# Power_Supply.net
KiCad netlist of a schematic drawn in Altium Designer
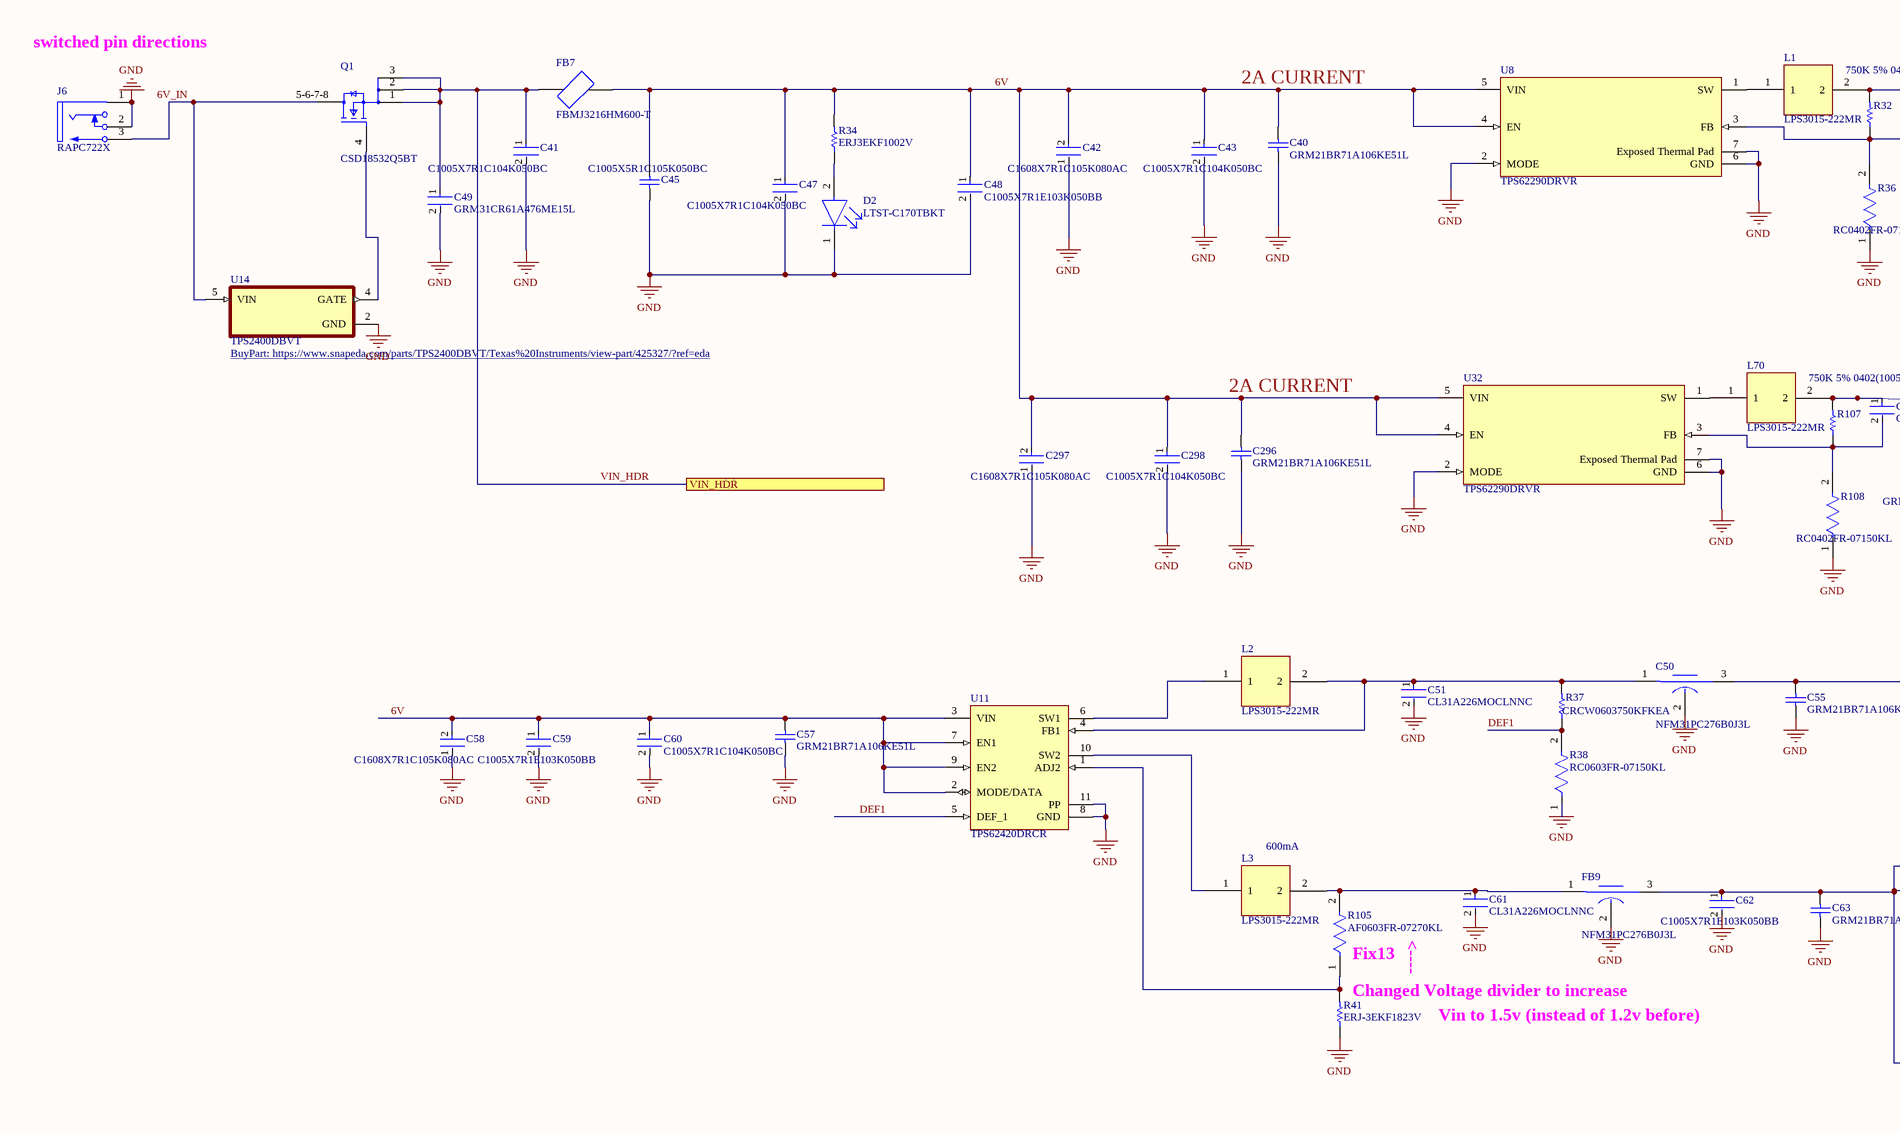
[diagram p0: Power_Supply.SchDoc, top left]
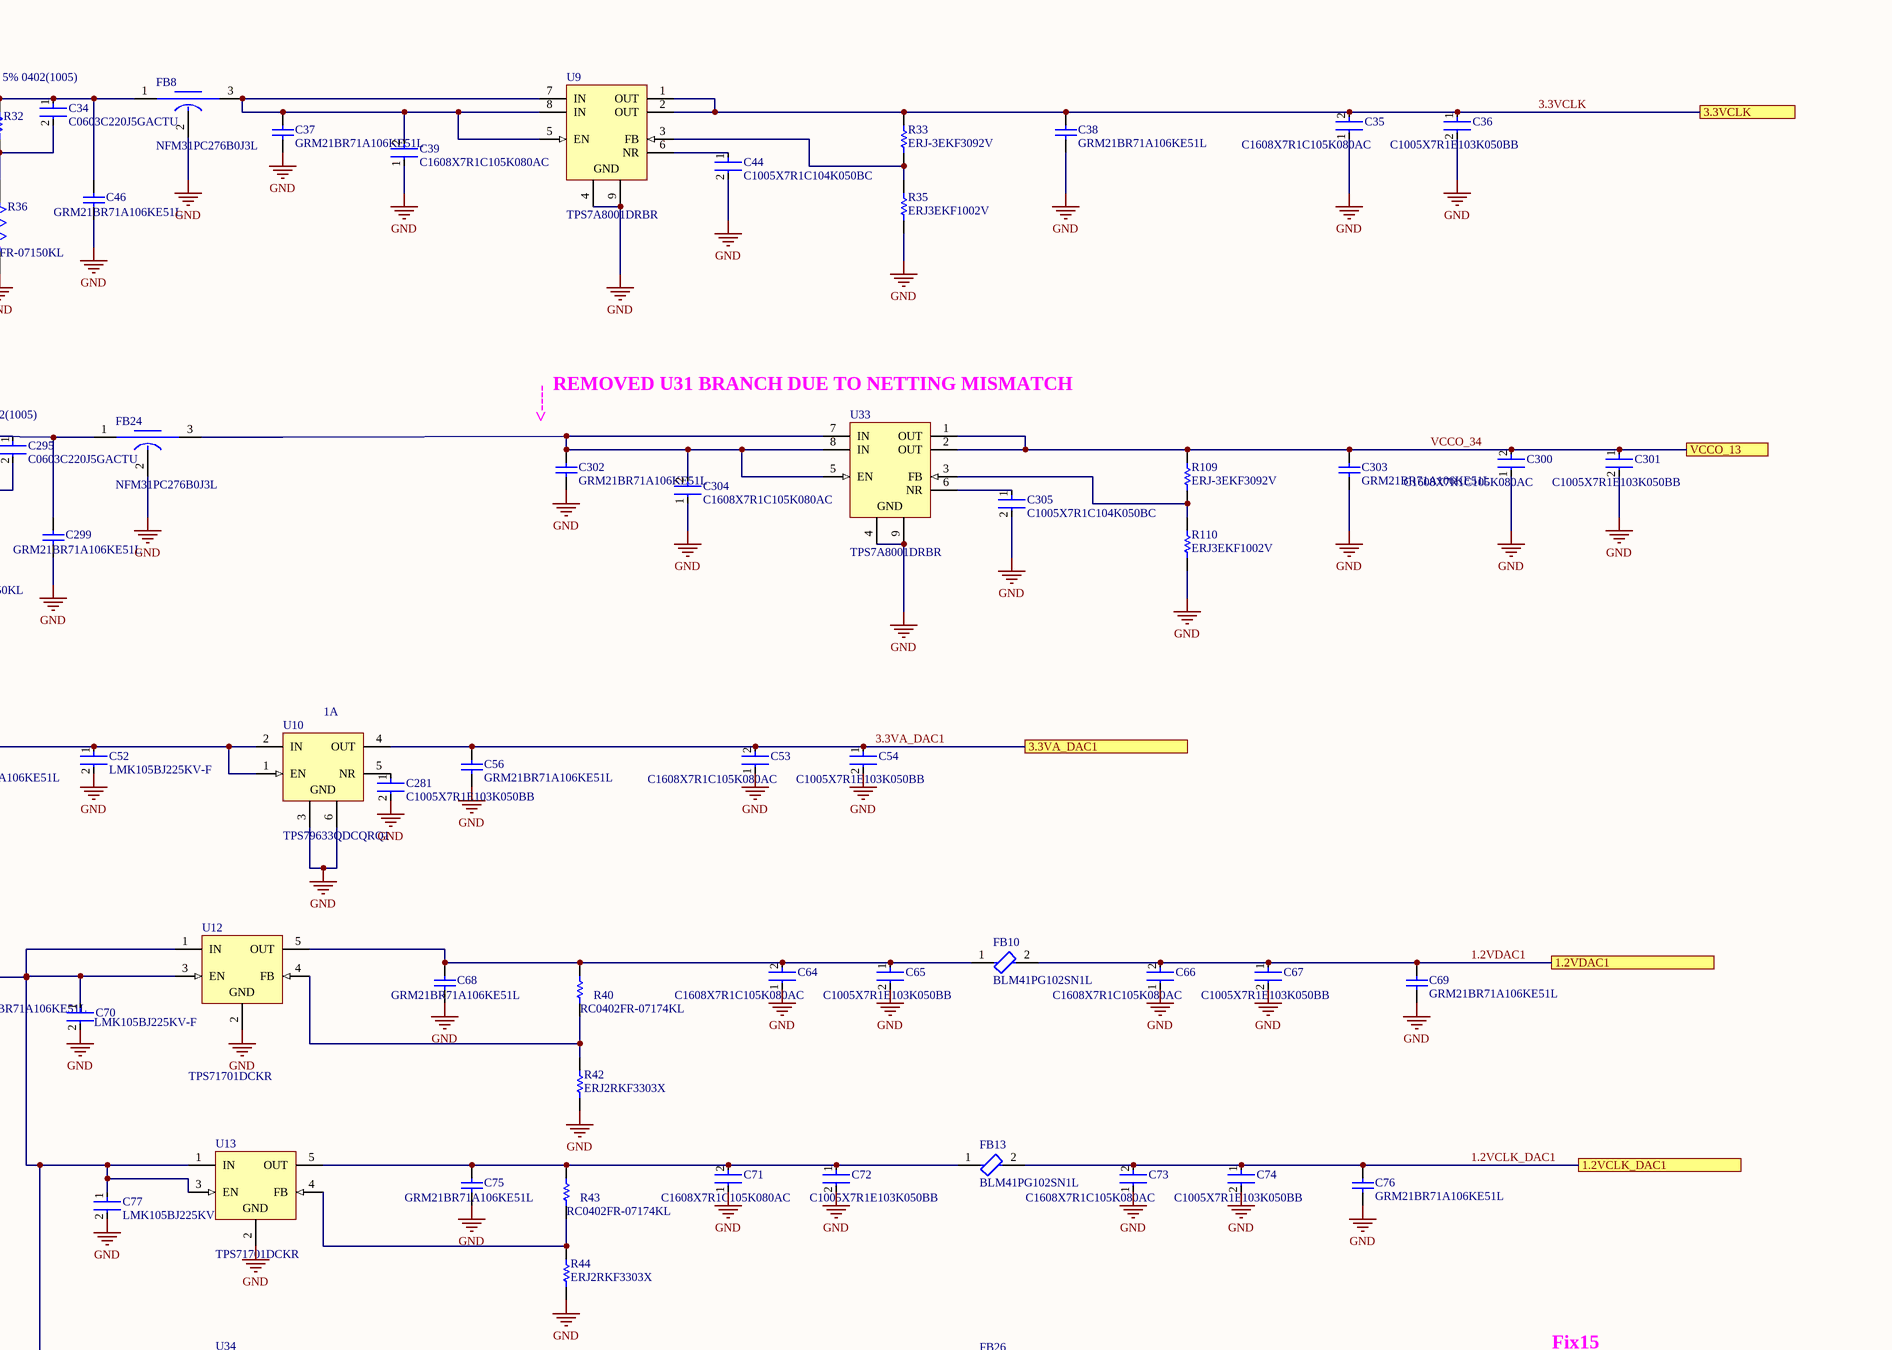
[diagram p1: Power_Supply.SchDoc, top right]
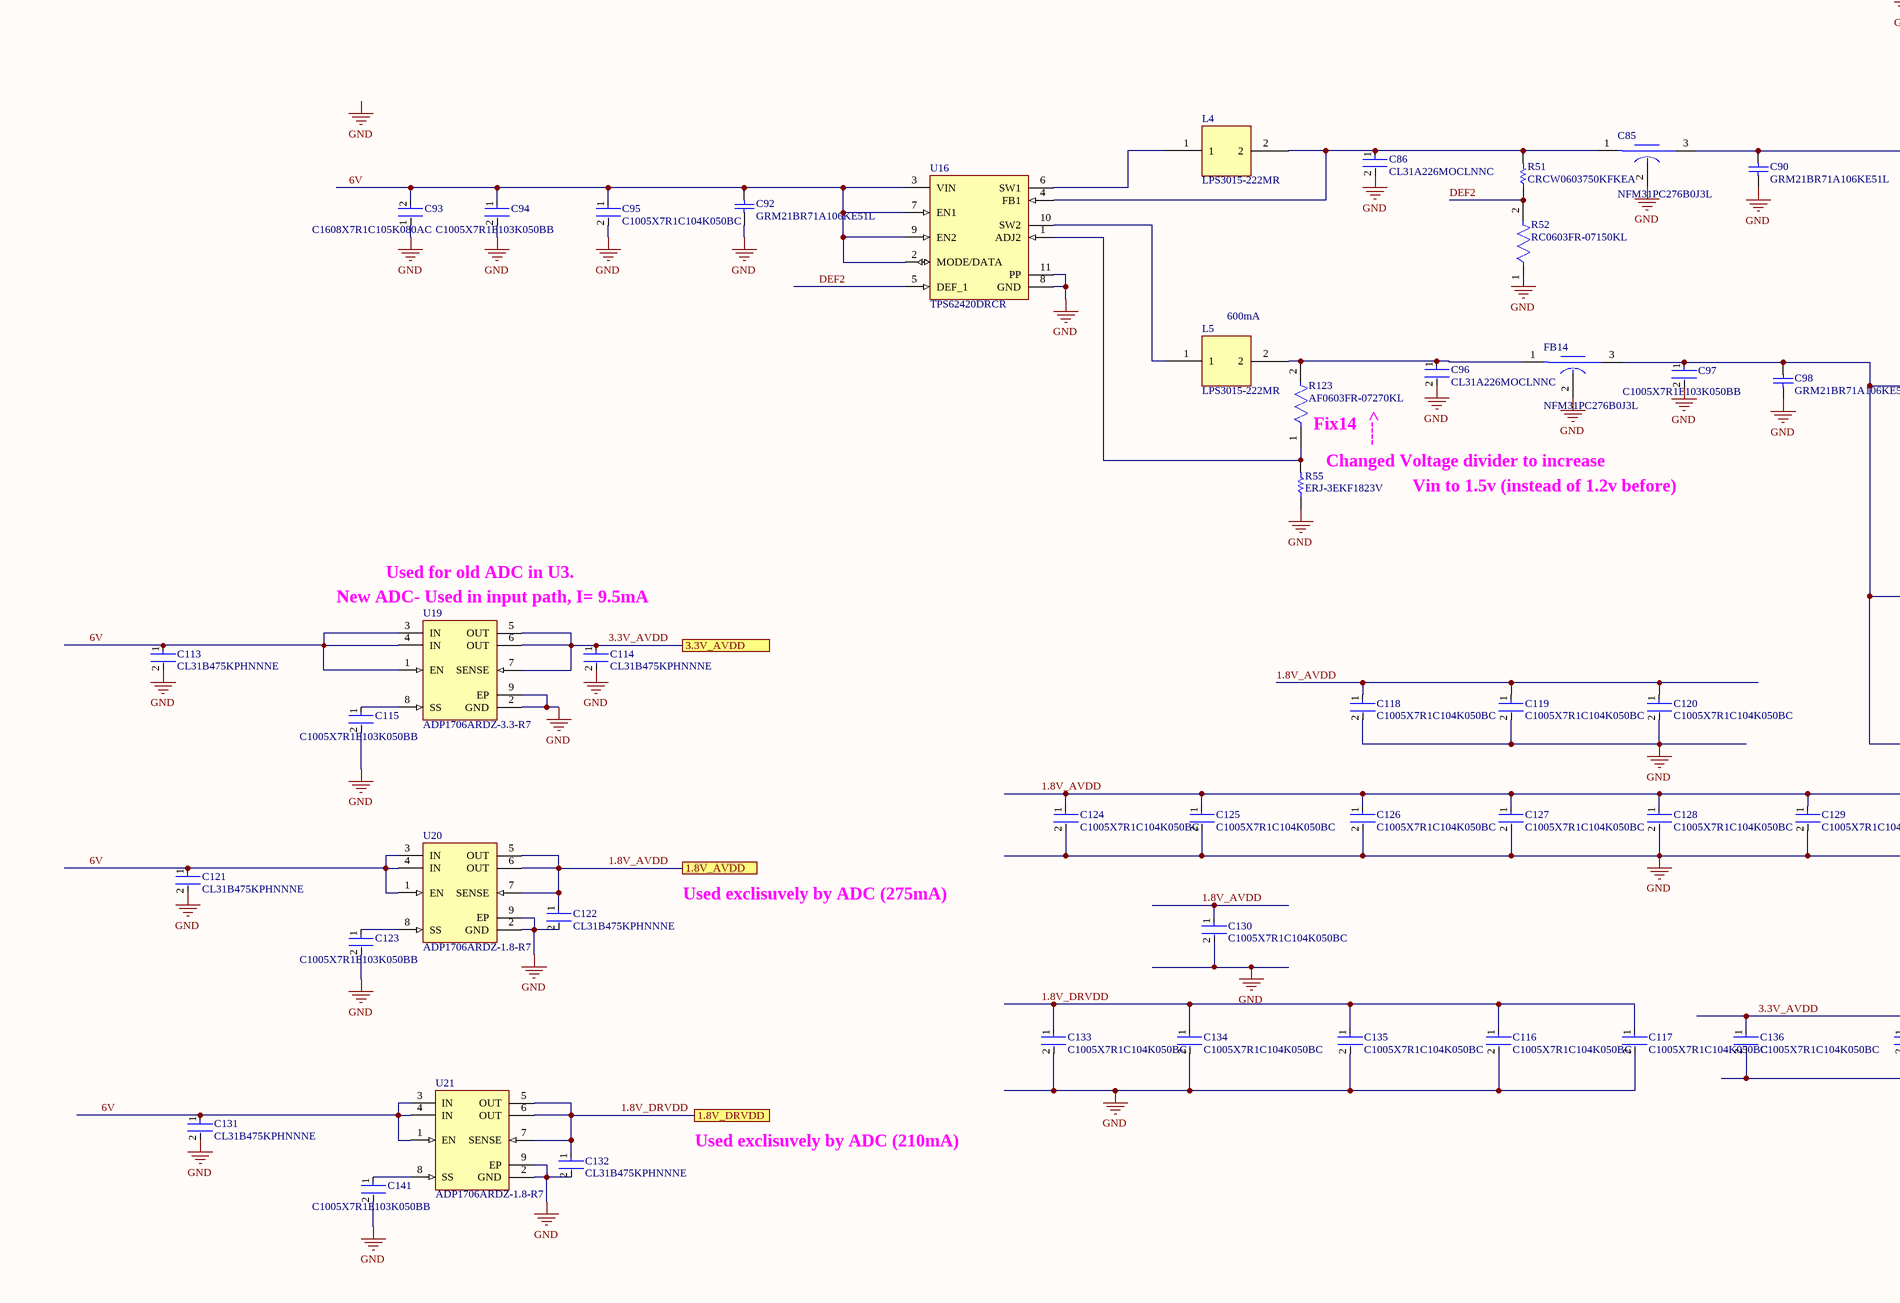
[diagram p2: Power_Supply.SchDoc, bottom left]
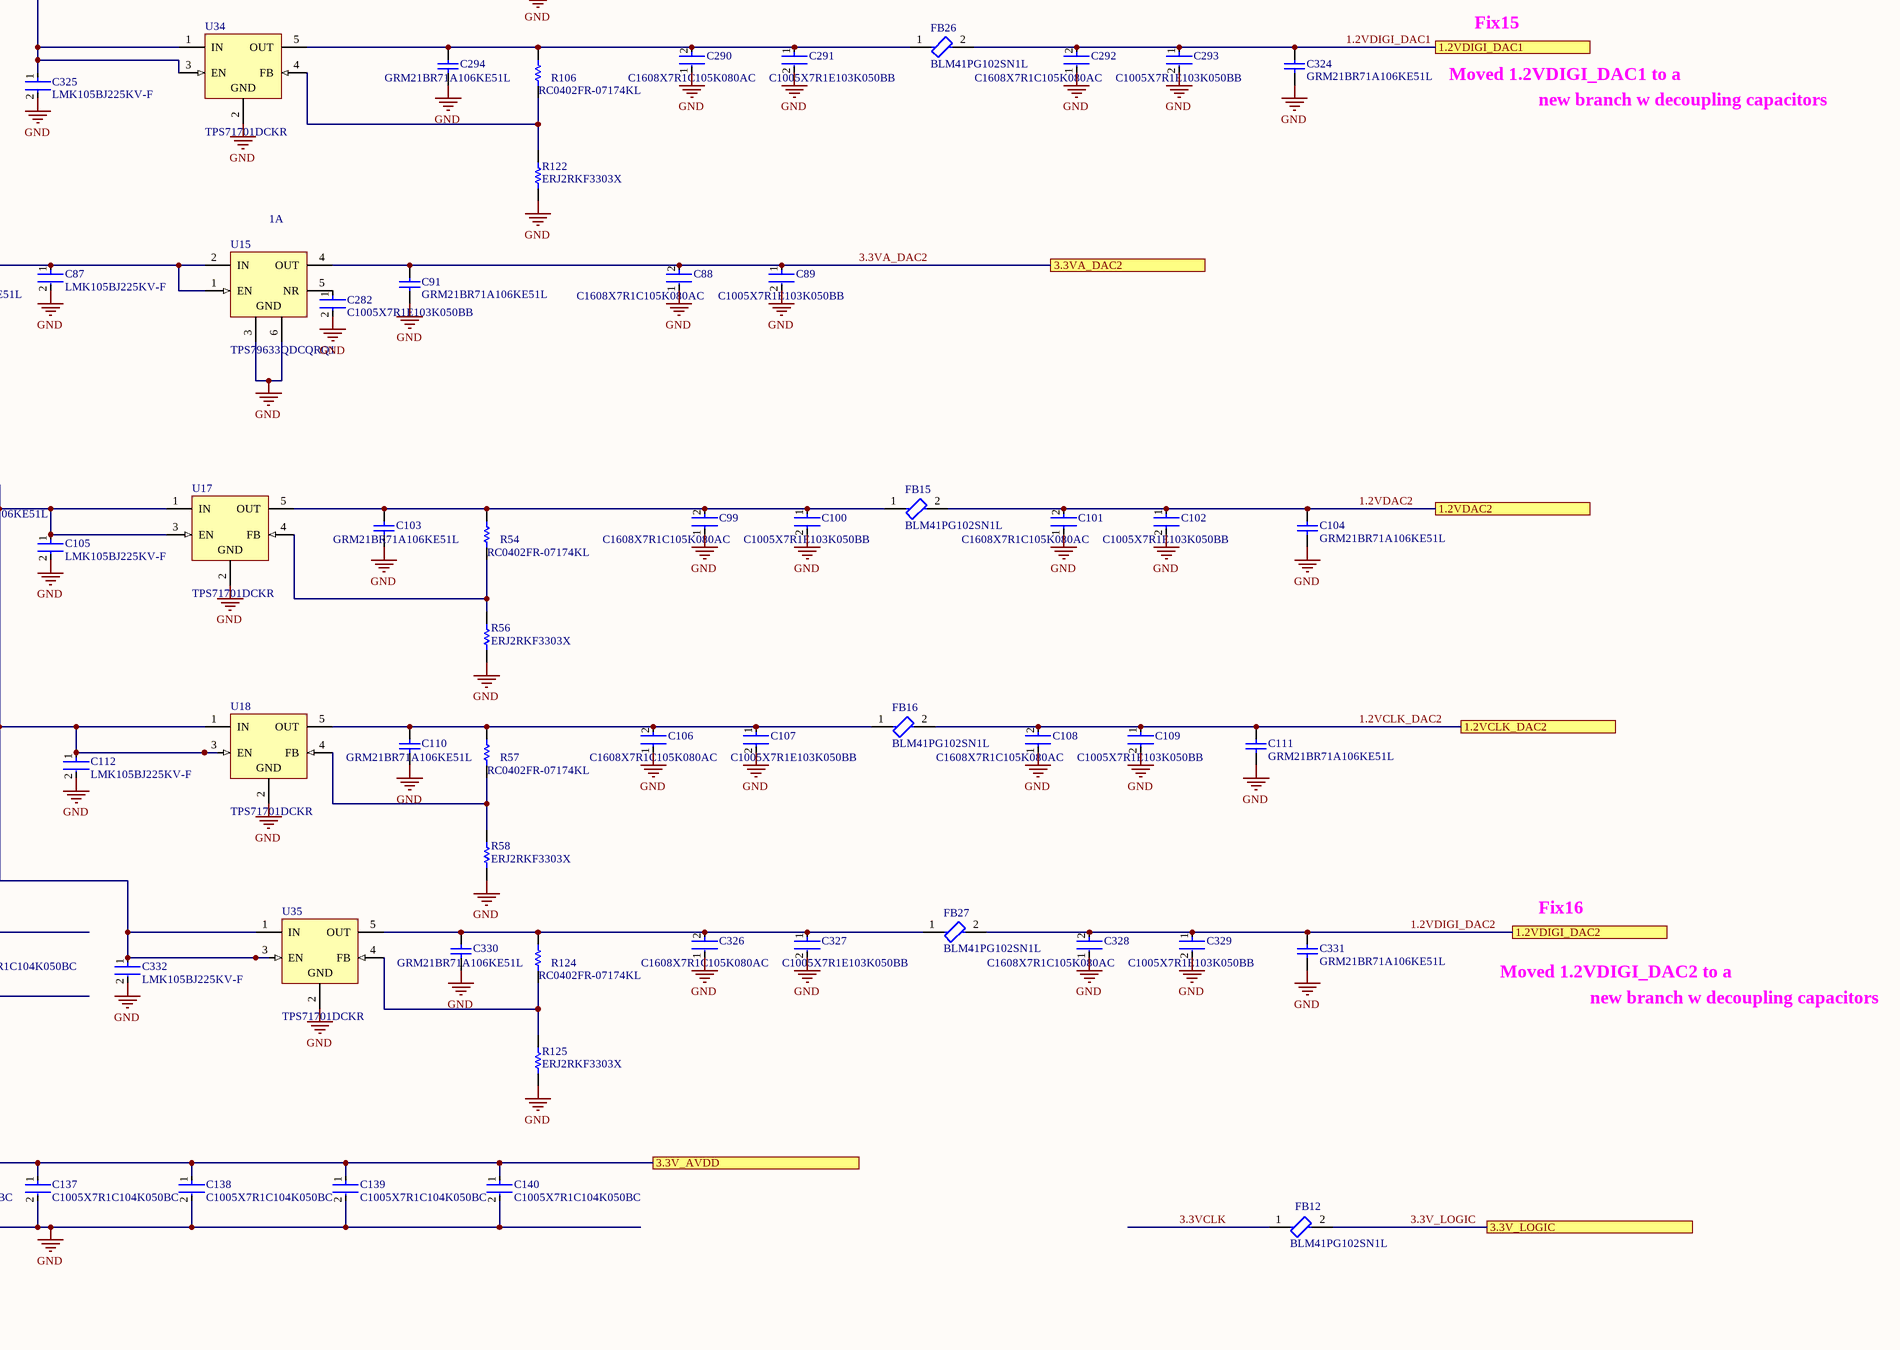
[diagram p3: Power_Supply.SchDoc, bottom right]

(export (version "E")
  (design (tool "Eeschema 10.0.6"))
  (components
    (comp (ref "C34")
      (value "C0603C220J5GACTU")
      (footprint "C0603")
      (description "Cap Ceramic 22pF 50V C0G 5% SMD 0603 125°C Paper T/R")
      (fields (field (name "TOLERANCE") "0.05") (field (name "MANUFACTURER") "KEMET"))
      (libsource (lib "DACֹֹ_Sources") (part "b4654b650e69147ec39a6b967a45e02"))
    )
    (comp (ref "C35")
      (value "C1608X7R1C105K080AC")
      (footprint "C0603")
      (description "Multilayer Ceramic Capacitors 1μF ±10% 16V X7R SMD 0603")
      (fields (field (name "VOLTAGE") "16V") (field (name "TOLERANCE") "10%"))
      (libsource (lib "DACֹֹ_Sources") (part "236180d848d6139a670b325ea6854c9"))
    )
    (comp (ref "C36")
      (value "C1005X7R1E103K050BB")
      (footprint "C0402")
      (description "Multilayer Ceramic Capacitors 10nF ±10% 25V X7R SMD 0402")
      (fields (field (name "TOLERANCE") "10%") (field (name "VOLTAGE") "25V"))
      (libsource (lib "DACֹֹ_Sources") (part "b4654b650e69147ec39a6b967a45e02"))
    )
    (comp (ref "C37")
      (value "GRM21BR71A106KE51L")
      (footprint "C0805")
      (fields (field (name "MANUFACTURER") "Murata"))
      (libsource (lib "DACֹֹ_Sources") (part "CAP"))
    )
    (comp (ref "C38")
      (value "GRM21BR71A106KE51L")
      (footprint "C0805")
      (fields (field (name "MANUFACTURER") "Murata"))
      (libsource (lib "DACֹֹ_Sources") (part "CAP"))
    )
    (comp (ref "C39")
      (value "C1608X7R1C105K080AC")
      (footprint "C0603")
      (description "Multilayer Ceramic Capacitors 1μF ±10% 16V X7R SMD 0603")
      (fields (field (name "VOLTAGE") "16V") (field (name "TOLERANCE") "10%"))
      (libsource (lib "DACֹֹ_Sources") (part "236180d848d6139a670b325ea6854c9"))
    )
    (comp (ref "C40")
      (value "GRM21BR71A106KE51L")
      (footprint "C0805")
      (fields (field (name "MANUFACTURER") "Murata"))
      (libsource (lib "DACֹֹ_Sources") (part "CAP"))
    )
    (comp (ref "C41")
      (value "C1005X7R1C104K050BC")
      (footprint "C0402")
      (description "Multilayer Ceramic Capacitors 100nF ±10% 16V X7R SMD 0402")
      (fields (field (name "VOLTAGE") "16V") (field (name "TOLERANCE") "10%"))
      (libsource (lib "DACֹֹ_Sources") (part "b4654b650e69147ec39a6b967a45e02"))
    )
    (comp (ref "C42")
      (value "C1608X7R1C105K080AC")
      (footprint "C0603")
      (description "Multilayer Ceramic Capacitors 1μF ±10% 16V X7R SMD 0603")
      (fields (field (name "VOLTAGE") "16V") (field (name "TOLERANCE") "10%"))
      (libsource (lib "DACֹֹ_Sources") (part "236180d848d6139a670b325ea6854c9"))
    )
    (comp (ref "C43")
      (value "C1005X7R1C104K050BC")
      (footprint "C0402")
      (description "Multilayer Ceramic Capacitors 100nF ±10% 16V X7R SMD 0402")
      (fields (field (name "VOLTAGE") "16V") (field (name "TOLERANCE") "10%"))
      (libsource (lib "DACֹֹ_Sources") (part "b4654b650e69147ec39a6b967a45e02"))
    )
    (comp (ref "C44")
      (value "C1005X7R1C104K050BC")
      (footprint "C0402")
      (description "Multilayer Ceramic Capacitors 100nF ±10% 16V X7R SMD 0402")
      (fields (field (name "VOLTAGE") "16V") (field (name "TOLERANCE") "10%"))
      (libsource (lib "DACֹֹ_Sources") (part "b4654b650e69147ec39a6b967a45e02"))
    )
    (comp (ref "C45")
      (value "C1005X5R1C105K050BC")
      (footprint "C0402")
      (description "Chip Capacitor, 1 uF, +/- 10%, 16 V, -55 to 85 degC, 0402 (1005 Metric), RoHS, Tape and Reel")
      (fields
        (field (name "TOLERANCE") "±10%")
        (field (name "PCN PART NUMBER") "MLCCPartNumberChange30/Nov/2012")
      )
      (libsource (lib "DACֹֹ_Sources") (part "CAP-NP-2"))
    )
    (comp (ref "C46")
      (value "GRM21BR71A106KE51L")
      (footprint "C0805")
      (fields (field (name "MANUFACTURER") "Murata"))
      (libsource (lib "DACֹֹ_Sources") (part "CAP"))
    )
    (comp (ref "C47")
      (value "C1005X7R1C104K050BC")
      (footprint "C0402")
      (description "Multilayer Ceramic Capacitors 100nF ±10% 16V X7R SMD 0402")
      (fields (field (name "VOLTAGE") "16V") (field (name "TOLERANCE") "10%"))
      (libsource (lib "DACֹֹ_Sources") (part "b4654b650e69147ec39a6b967a45e02"))
    )
    (comp (ref "C48")
      (value "C1005X7R1E103K050BB")
      (footprint "C0402")
      (description "Multilayer Ceramic Capacitors 10nF ±10% 25V X7R SMD 0402")
      (fields (field (name "TOLERANCE") "10%") (field (name "VOLTAGE") "25V"))
      (libsource (lib "DACֹֹ_Sources") (part "b4654b650e69147ec39a6b967a45e02"))
    )
    (comp (ref "C49")
      (value "GRM31CR61A476ME15L")
      (footprint "C1206")
      (description "Chip Multilayer Ceramic Capacitors for General Purpose, 1206, 47uF, X5R, 15%, 20%, 10V")
      (fields (field (name "TOLERANCE") "20%") (field (name "VOLTAGE") "10V"))
      (libsource (lib "DACֹֹ_Sources") (part "02cd4be3c70576c341d710602a673aa"))
    )
    (comp (ref "C50")
      (value "NFM31PC276B0J3L")
      (footprint "FP-NFM31-0_2-MFG")
      (fields (field (name "VOLTAGE") "6.3V") (field (name "TOLERANCE") "20%"))
      (libsource (lib "DACֹֹ_Sources") (part "968ca41a07abfef6fd4f7114a56c54f"))
    )
    (comp (ref "C51")
      (value "CL31A226MOCLNNC")
      (footprint "C1206")
      (description "Cap Ceramic 22uF 16V X5R ±20% SMD 1206 +85°C Embossed T/R")
      (fields (field (name "TOLERANCE") "20%") (field (name "VOLTAGE") "16V"))
      (libsource (lib "DACֹֹ_Sources") (part "b4654b650e69147ec39a6b967a45e02"))
    )
    (comp (ref "C52")
      (value "LMK105BJ225KV-F")
      (footprint "C0402")
      (description "None")
      (fields (field (name "TOLERANCE") "10%"))
      (libsource (lib "DACֹֹ_Sources") (part "b4654b650e69147ec39a6b967a45e02"))
    )
    (comp (ref "C53")
      (value "C1608X7R1C105K080AC")
      (footprint "C0603")
      (description "Multilayer Ceramic Capacitors 1μF ±10% 16V X7R SMD 0603")
      (fields (field (name "VOLTAGE") "16V") (field (name "TOLERANCE") "10%"))
      (libsource (lib "DACֹֹ_Sources") (part "236180d848d6139a670b325ea6854c9"))
    )
    (comp (ref "C54")
      (value "C1005X7R1E103K050BB")
      (footprint "C0402")
      (description "Multilayer Ceramic Capacitors 10nF ±10% 25V X7R SMD 0402")
      (fields (field (name "TOLERANCE") "10%") (field (name "VOLTAGE") "25V"))
      (libsource (lib "DACֹֹ_Sources") (part "b4654b650e69147ec39a6b967a45e02"))
    )
    (comp (ref "C55")
      (value "GRM21BR71A106KE51L")
      (footprint "C0805")
      (fields (field (name "MANUFACTURER") "Murata"))
      (libsource (lib "DACֹֹ_Sources") (part "CAP"))
    )
    (comp (ref "C56")
      (value "GRM21BR71A106KE51L")
      (footprint "C0805")
      (fields (field (name "MANUFACTURER") "Murata"))
      (libsource (lib "DACֹֹ_Sources") (part "CAP"))
    )
    (comp (ref "C57")
      (value "GRM21BR71A106KE51L")
      (footprint "C0805")
      (fields (field (name "MANUFACTURER") "Murata"))
      (libsource (lib "DACֹֹ_Sources") (part "CAP"))
    )
    (comp (ref "C58")
      (value "C1608X7R1C105K080AC")
      (footprint "C0603")
      (description "Multilayer Ceramic Capacitors 1μF ±10% 16V X7R SMD 0603")
      (fields (field (name "VOLTAGE") "16V") (field (name "TOLERANCE") "10%"))
      (libsource (lib "DACֹֹ_Sources") (part "236180d848d6139a670b325ea6854c9"))
    )
    (comp (ref "C59")
      (value "C1005X7R1E103K050BB")
      (footprint "C0402")
      (description "Multilayer Ceramic Capacitors 10nF ±10% 25V X7R SMD 0402")
      (fields (field (name "TOLERANCE") "10%") (field (name "VOLTAGE") "25V"))
      (libsource (lib "DACֹֹ_Sources") (part "b4654b650e69147ec39a6b967a45e02"))
    )
    (comp (ref "C60")
      (value "C1005X7R1C104K050BC")
      (footprint "C0402")
      (description "Multilayer Ceramic Capacitors 100nF ±10% 16V X7R SMD 0402")
      (fields (field (name "VOLTAGE") "16V") (field (name "TOLERANCE") "10%"))
      (libsource (lib "DACֹֹ_Sources") (part "b4654b650e69147ec39a6b967a45e02"))
    )
    (comp (ref "C61")
      (value "CL31A226MOCLNNC")
      (footprint "C1206")
      (description "Cap Ceramic 22uF 16V X5R ±20% SMD 1206 +85°C Embossed T/R")
      (fields (field (name "TOLERANCE") "20%") (field (name "VOLTAGE") "16V"))
      (libsource (lib "DACֹֹ_Sources") (part "b4654b650e69147ec39a6b967a45e02"))
    )
    (comp (ref "C62")
      (value "C1005X7R1E103K050BB")
      (footprint "C0402")
      (description "Multilayer Ceramic Capacitors 10nF ±10% 25V X7R SMD 0402")
      (fields (field (name "TOLERANCE") "10%") (field (name "VOLTAGE") "25V"))
      (libsource (lib "DACֹֹ_Sources") (part "b4654b650e69147ec39a6b967a45e02"))
    )
    (comp (ref "C63")
      (value "GRM21BR71A106KE51L")
      (footprint "C0805")
      (fields (field (name "MANUFACTURER") "Murata"))
      (libsource (lib "DACֹֹ_Sources") (part "CAP"))
    )
    (comp (ref "C64")
      (value "C1608X7R1C105K080AC")
      (footprint "C0603")
      (description "Multilayer Ceramic Capacitors 1μF ±10% 16V X7R SMD 0603")
      (fields (field (name "VOLTAGE") "16V") (field (name "TOLERANCE") "10%"))
      (libsource (lib "DACֹֹ_Sources") (part "236180d848d6139a670b325ea6854c9"))
    )
    (comp (ref "C65")
      (value "C1005X7R1E103K050BB")
      (footprint "C0402")
      (description "Multilayer Ceramic Capacitors 10nF ±10% 25V X7R SMD 0402")
      (fields (field (name "TOLERANCE") "10%") (field (name "VOLTAGE") "25V"))
      (libsource (lib "DACֹֹ_Sources") (part "b4654b650e69147ec39a6b967a45e02"))
    )
    (comp (ref "C66")
      (value "C1608X7R1C105K080AC")
      (footprint "C0603")
      (description "Multilayer Ceramic Capacitors 1μF ±10% 16V X7R SMD 0603")
      (fields (field (name "VOLTAGE") "16V") (field (name "TOLERANCE") "10%"))
      (libsource (lib "DACֹֹ_Sources") (part "236180d848d6139a670b325ea6854c9"))
    )
    (comp (ref "C67")
      (value "C1005X7R1E103K050BB")
      (footprint "C0402")
      (description "Multilayer Ceramic Capacitors 10nF ±10% 25V X7R SMD 0402")
      (fields (field (name "TOLERANCE") "10%") (field (name "VOLTAGE") "25V"))
      (libsource (lib "DACֹֹ_Sources") (part "b4654b650e69147ec39a6b967a45e02"))
    )
    (comp (ref "C68")
      (value "GRM21BR71A106KE51L")
      (footprint "C0805")
      (fields (field (name "MANUFACTURER") "Murata"))
      (libsource (lib "DACֹֹ_Sources") (part "CAP"))
    )
    (comp (ref "C69")
      (value "GRM21BR71A106KE51L")
      (footprint "C0805")
      (fields (field (name "MANUFACTURER") "Murata"))
      (libsource (lib "DACֹֹ_Sources") (part "CAP"))
    )
    (comp (ref "C70")
      (value "LMK105BJ225KV-F")
      (footprint "C0402")
      (description "None")
      (fields (field (name "TOLERANCE") "10%"))
      (libsource (lib "Simulation Generic Components") (part "b4654b650e69147ec39a6b967a45e02"))
    )
    (comp (ref "C71")
      (value "C1608X7R1C105K080AC")
      (footprint "C0603")
      (description "Multilayer Ceramic Capacitors 1μF ±10% 16V X7R SMD 0603")
      (fields (field (name "VOLTAGE") "16V") (field (name "TOLERANCE") "10%"))
      (libsource (lib "DACֹֹ_Sources") (part "236180d848d6139a670b325ea6854c9"))
    )
    (comp (ref "C72")
      (value "C1005X7R1E103K050BB")
      (footprint "C0402")
      (description "Multilayer Ceramic Capacitors 10nF ±10% 25V X7R SMD 0402")
      (fields (field (name "TOLERANCE") "10%") (field (name "VOLTAGE") "25V"))
      (libsource (lib "DACֹֹ_Sources") (part "b4654b650e69147ec39a6b967a45e02"))
    )
    (comp (ref "C73")
      (value "C1608X7R1C105K080AC")
      (footprint "C0603")
      (description "Multilayer Ceramic Capacitors 1μF ±10% 16V X7R SMD 0603")
      (fields (field (name "VOLTAGE") "16V") (field (name "TOLERANCE") "10%"))
      (libsource (lib "DACֹֹ_Sources") (part "236180d848d6139a670b325ea6854c9"))
    )
    (comp (ref "C74")
      (value "C1005X7R1E103K050BB")
      (footprint "C0402")
      (description "Multilayer Ceramic Capacitors 10nF ±10% 25V X7R SMD 0402")
      (fields (field (name "TOLERANCE") "10%") (field (name "VOLTAGE") "25V"))
      (libsource (lib "DACֹֹ_Sources") (part "b4654b650e69147ec39a6b967a45e02"))
    )
    (comp (ref "C75")
      (value "GRM21BR71A106KE51L")
      (footprint "C0805")
      (fields (field (name "MANUFACTURER") "Murata"))
      (libsource (lib "DACֹֹ_Sources") (part "CAP"))
    )
    (comp (ref "C76")
      (value "GRM21BR71A106KE51L")
      (footprint "C0805")
      (fields (field (name "MANUFACTURER") "Murata"))
      (libsource (lib "DACֹֹ_Sources") (part "CAP"))
    )
    (comp (ref "C77")
      (value "LMK105BJ225KV-F")
      (footprint "C0402")
      (description "None")
      (fields (field (name "TOLERANCE") "10%"))
      (libsource (lib "DACֹֹ_Sources") (part "b4654b650e69147ec39a6b967a45e02"))
    )
    (comp (ref "C85")
      (value "NFM31PC276B0J3L")
      (footprint "FP-NFM31-0_2-MFG")
      (fields (field (name "VOLTAGE") "6.3V") (field (name "TOLERANCE") "20%"))
      (libsource (lib "DACֹֹ_Sources") (part "968ca41a07abfef6fd4f7114a56c54f"))
    )
    (comp (ref "C86")
      (value "CL31A226MOCLNNC")
      (footprint "C1206")
      (description "Cap Ceramic 22uF 16V X5R ±20% SMD 1206 +85°C Embossed T/R")
      (fields (field (name "TOLERANCE") "20%") (field (name "VOLTAGE") "16V"))
      (libsource (lib "DACֹֹ_Sources") (part "b4654b650e69147ec39a6b967a45e02"))
    )
    (comp (ref "C87")
      (value "LMK105BJ225KV-F")
      (footprint "C0402")
      (description "None")
      (fields (field (name "TOLERANCE") "10%"))
      (libsource (lib "DACֹֹ_Sources") (part "b4654b650e69147ec39a6b967a45e02"))
    )
    (comp (ref "C88")
      (value "C1608X7R1C105K080AC")
      (footprint "C0603")
      (description "Multilayer Ceramic Capacitors 1μF ±10% 16V X7R SMD 0603")
      (fields (field (name "VOLTAGE") "16V") (field (name "TOLERANCE") "10%"))
      (libsource (lib "DACֹֹ_Sources") (part "236180d848d6139a670b325ea6854c9"))
    )
    (comp (ref "C89")
      (value "C1005X7R1E103K050BB")
      (footprint "C0402")
      (description "Multilayer Ceramic Capacitors 10nF ±10% 25V X7R SMD 0402")
      (fields (field (name "TOLERANCE") "10%") (field (name "VOLTAGE") "25V"))
      (libsource (lib "DACֹֹ_Sources") (part "b4654b650e69147ec39a6b967a45e02"))
    )
    (comp (ref "C90")
      (value "GRM21BR71A106KE51L")
      (footprint "C0805")
      (fields (field (name "MANUFACTURER") "Murata"))
      (libsource (lib "DACֹֹ_Sources") (part "CAP"))
    )
    (comp (ref "C91")
      (value "GRM21BR71A106KE51L")
      (footprint "C0805")
      (fields (field (name "MANUFACTURER") "Murata"))
      (libsource (lib "DACֹֹ_Sources") (part "CAP"))
    )
    (comp (ref "C92")
      (value "GRM21BR71A106KE51L")
      (footprint "C0805")
      (fields (field (name "MANUFACTURER") "Murata"))
      (libsource (lib "DACֹֹ_Sources") (part "CAP"))
    )
    (comp (ref "C93")
      (value "C1608X7R1C105K080AC")
      (footprint "C0603")
      (description "Multilayer Ceramic Capacitors 1μF ±10% 16V X7R SMD 0603")
      (fields (field (name "VOLTAGE") "16V") (field (name "TOLERANCE") "10%"))
      (libsource (lib "DACֹֹ_Sources") (part "236180d848d6139a670b325ea6854c9"))
    )
    (comp (ref "C94")
      (value "C1005X7R1E103K050BB")
      (footprint "C0402")
      (description "Multilayer Ceramic Capacitors 10nF ±10% 25V X7R SMD 0402")
      (fields (field (name "TOLERANCE") "10%") (field (name "VOLTAGE") "25V"))
      (libsource (lib "DACֹֹ_Sources") (part "b4654b650e69147ec39a6b967a45e02"))
    )
    (comp (ref "C95")
      (value "C1005X7R1C104K050BC")
      (footprint "C0402")
      (description "Multilayer Ceramic Capacitors 100nF ±10% 16V X7R SMD 0402")
      (fields (field (name "VOLTAGE") "16V") (field (name "TOLERANCE") "10%"))
      (libsource (lib "DACֹֹ_Sources") (part "b4654b650e69147ec39a6b967a45e02"))
    )
    (comp (ref "C96")
      (value "CL31A226MOCLNNC")
      (footprint "C1206")
      (description "Cap Ceramic 22uF 16V X5R ±20% SMD 1206 +85°C Embossed T/R")
      (fields (field (name "TOLERANCE") "20%") (field (name "VOLTAGE") "16V"))
      (libsource (lib "DACֹֹ_Sources") (part "b4654b650e69147ec39a6b967a45e02"))
    )
    (comp (ref "C97")
      (value "C1005X7R1E103K050BB")
      (footprint "C0402")
      (description "Multilayer Ceramic Capacitors 10nF ±10% 25V X7R SMD 0402")
      (fields (field (name "TOLERANCE") "10%") (field (name "VOLTAGE") "25V"))
      (libsource (lib "DACֹֹ_Sources") (part "b4654b650e69147ec39a6b967a45e02"))
    )
    (comp (ref "C98")
      (value "GRM21BR71A106KE51L")
      (footprint "C0805")
      (fields (field (name "MANUFACTURER") "Murata"))
      (libsource (lib "DACֹֹ_Sources") (part "CAP"))
    )
    (comp (ref "C99")
      (value "C1608X7R1C105K080AC")
      (footprint "C0603")
      (description "Multilayer Ceramic Capacitors 1μF ±10% 16V X7R SMD 0603")
      (fields (field (name "VOLTAGE") "16V") (field (name "TOLERANCE") "10%"))
      (libsource (lib "DACֹֹ_Sources") (part "236180d848d6139a670b325ea6854c9"))
    )
    (comp (ref "C100")
      (value "C1005X7R1E103K050BB")
      (footprint "C0402")
      (description "Multilayer Ceramic Capacitors 10nF ±10% 25V X7R SMD 0402")
      (fields (field (name "TOLERANCE") "10%") (field (name "VOLTAGE") "25V"))
      (libsource (lib "DACֹֹ_Sources") (part "b4654b650e69147ec39a6b967a45e02"))
    )
    (comp (ref "C101")
      (value "C1608X7R1C105K080AC")
      (footprint "C0603")
      (description "Multilayer Ceramic Capacitors 1μF ±10% 16V X7R SMD 0603")
      (fields (field (name "VOLTAGE") "16V") (field (name "TOLERANCE") "10%"))
      (libsource (lib "DACֹֹ_Sources") (part "236180d848d6139a670b325ea6854c9"))
    )
    (comp (ref "C102")
      (value "C1005X7R1E103K050BB")
      (footprint "C0402")
      (description "Multilayer Ceramic Capacitors 10nF ±10% 25V X7R SMD 0402")
      (fields (field (name "TOLERANCE") "10%") (field (name "VOLTAGE") "25V"))
      (libsource (lib "DACֹֹ_Sources") (part "b4654b650e69147ec39a6b967a45e02"))
    )
    (comp (ref "C103")
      (value "GRM21BR71A106KE51L")
      (footprint "C0805")
      (fields (field (name "MANUFACTURER") "Murata"))
      (libsource (lib "DACֹֹ_Sources") (part "CAP"))
    )
    (comp (ref "C104")
      (value "GRM21BR71A106KE51L")
      (footprint "C0805")
      (fields (field (name "MANUFACTURER") "Murata"))
      (libsource (lib "DACֹֹ_Sources") (part "CAP"))
    )
    (comp (ref "C105")
      (value "LMK105BJ225KV-F")
      (footprint "C0402")
      (description "None")
      (fields (field (name "TOLERANCE") "10%"))
      (libsource (lib "DACֹֹ_Sources") (part "b4654b650e69147ec39a6b967a45e02"))
    )
    (comp (ref "C106")
      (value "C1608X7R1C105K080AC")
      (footprint "C0603")
      (description "Multilayer Ceramic Capacitors 1μF ±10% 16V X7R SMD 0603")
      (fields (field (name "VOLTAGE") "16V") (field (name "TOLERANCE") "10%"))
      (libsource (lib "DACֹֹ_Sources") (part "236180d848d6139a670b325ea6854c9"))
    )
    (comp (ref "C107")
      (value "C1005X7R1E103K050BB")
      (footprint "C0402")
      (description "Multilayer Ceramic Capacitors 10nF ±10% 25V X7R SMD 0402")
      (fields (field (name "TOLERANCE") "10%") (field (name "VOLTAGE") "25V"))
      (libsource (lib "DACֹֹ_Sources") (part "b4654b650e69147ec39a6b967a45e02"))
    )
    (comp (ref "C108")
      (value "C1608X7R1C105K080AC")
      (footprint "C0603")
      (description "Multilayer Ceramic Capacitors 1μF ±10% 16V X7R SMD 0603")
      (fields (field (name "VOLTAGE") "16V") (field (name "TOLERANCE") "10%"))
      (libsource (lib "DACֹֹ_Sources") (part "236180d848d6139a670b325ea6854c9"))
    )
    (comp (ref "C109")
      (value "C1005X7R1E103K050BB")
      (footprint "C0402")
      (description "Multilayer Ceramic Capacitors 10nF ±10% 25V X7R SMD 0402")
      (fields (field (name "TOLERANCE") "10%") (field (name "VOLTAGE") "25V"))
      (libsource (lib "DACֹֹ_Sources") (part "b4654b650e69147ec39a6b967a45e02"))
    )
    (comp (ref "C110")
      (value "GRM21BR71A106KE51L")
      (footprint "C0805")
      (fields (field (name "MANUFACTURER") "Murata"))
      (libsource (lib "DACֹֹ_Sources") (part "CAP"))
    )
    (comp (ref "C111")
      (value "GRM21BR71A106KE51L")
      (footprint "C0805")
      (fields (field (name "MANUFACTURER") "Murata"))
      (libsource (lib "DACֹֹ_Sources") (part "CAP"))
    )
    (comp (ref "C112")
      (value "LMK105BJ225KV-F")
      (footprint "C0402")
      (description "None")
      (fields (field (name "TOLERANCE") "10%"))
      (libsource (lib "DACֹֹ_Sources") (part "b4654b650e69147ec39a6b967a45e02"))
    )
    (comp (ref "C113")
      (value "CL31B475KPHNNNE")
      (footprint "C1206")
      (description "Cap Ceramic 4.7uF 10V X7R ±10% SMD 1206 +125°C Embossed T/R")
      (fields (field (name "TOLERANCE") "10%") (field (name "VOLTAGE") "10V"))
      (libsource (lib "DACֹֹ_Sources") (part "b4654b650e69147ec39a6b967a45e02"))
    )
    (comp (ref "C114")
      (value "CL31B475KPHNNNE")
      (footprint "C1206")
      (description "Cap Ceramic 4.7uF 10V X7R ±10% SMD 1206 +125°C Embossed T/R")
      (fields (field (name "TOLERANCE") "10%") (field (name "VOLTAGE") "10V"))
      (libsource (lib "DACֹֹ_Sources") (part "b4654b650e69147ec39a6b967a45e02"))
    )
    (comp (ref "C115")
      (value "C1005X7R1E103K050BB")
      (footprint "C0402")
      (description "Multilayer Ceramic Capacitors 10nF ±10% 25V X7R SMD 0402")
      (fields (field (name "TOLERANCE") "10%") (field (name "VOLTAGE") "25V"))
      (libsource (lib "DACֹֹ_Sources") (part "b4654b650e69147ec39a6b967a45e02"))
    )
    (comp (ref "C116")
      (value "C1005X7R1C104K050BC")
      (footprint "C0402")
      (description "Multilayer Ceramic Capacitors 100nF ±10% 16V X7R SMD 0402")
      (fields (field (name "VOLTAGE") "16V") (field (name "TOLERANCE") "10%"))
      (libsource (lib "DACֹֹ_Sources") (part "b4654b650e69147ec39a6b967a45e02"))
    )
    (comp (ref "C117")
      (value "C1005X7R1C104K050BC")
      (footprint "C0402")
      (description "Multilayer Ceramic Capacitors 100nF ±10% 16V X7R SMD 0402")
      (fields (field (name "VOLTAGE") "16V") (field (name "TOLERANCE") "10%"))
      (libsource (lib "DACֹֹ_Sources") (part "b4654b650e69147ec39a6b967a45e02"))
    )
    (comp (ref "C118")
      (value "C1005X7R1C104K050BC")
      (footprint "C0402")
      (description "Multilayer Ceramic Capacitors 100nF ±10% 16V X7R SMD 0402")
      (fields (field (name "VOLTAGE") "16V") (field (name "TOLERANCE") "10%"))
      (libsource (lib "DACֹֹ_Sources") (part "b4654b650e69147ec39a6b967a45e02"))
    )
    (comp (ref "C119")
      (value "C1005X7R1C104K050BC")
      (footprint "C0402")
      (description "Multilayer Ceramic Capacitors 100nF ±10% 16V X7R SMD 0402")
      (fields (field (name "VOLTAGE") "16V") (field (name "TOLERANCE") "10%"))
      (libsource (lib "DACֹֹ_Sources") (part "b4654b650e69147ec39a6b967a45e02"))
    )
    (comp (ref "C120")
      (value "C1005X7R1C104K050BC")
      (footprint "C0402")
      (description "Multilayer Ceramic Capacitors 100nF ±10% 16V X7R SMD 0402")
      (fields (field (name "VOLTAGE") "16V") (field (name "TOLERANCE") "10%"))
      (libsource (lib "DACֹֹ_Sources") (part "b4654b650e69147ec39a6b967a45e02"))
    )
    (comp (ref "C121")
      (value "CL31B475KPHNNNE")
      (footprint "C1206")
      (description "Cap Ceramic 4.7uF 10V X7R ±10% SMD 1206 +125°C Embossed T/R")
      (fields (field (name "TOLERANCE") "10%") (field (name "VOLTAGE") "10V"))
      (libsource (lib "DACֹֹ_Sources") (part "b4654b650e69147ec39a6b967a45e02"))
    )
    (comp (ref "C122")
      (value "CL31B475KPHNNNE")
      (footprint "C1206")
      (description "Cap Ceramic 4.7uF 10V X7R ±10% SMD 1206 +125°C Embossed T/R")
      (fields (field (name "TOLERANCE") "10%") (field (name "VOLTAGE") "10V"))
      (libsource (lib "DACֹֹ_Sources") (part "b4654b650e69147ec39a6b967a45e02"))
    )
    (comp (ref "C123")
      (value "C1005X7R1E103K050BB")
      (footprint "C0402")
      (description "Multilayer Ceramic Capacitors 10nF ±10% 25V X7R SMD 0402")
      (fields (field (name "TOLERANCE") "10%") (field (name "VOLTAGE") "25V"))
      (libsource (lib "DACֹֹ_Sources") (part "b4654b650e69147ec39a6b967a45e02"))
    )
    (comp (ref "C124")
      (value "C1005X7R1C104K050BC")
      (footprint "C0402")
      (description "Multilayer Ceramic Capacitors 100nF ±10% 16V X7R SMD 0402")
      (fields (field (name "VOLTAGE") "16V") (field (name "TOLERANCE") "10%"))
      (libsource (lib "DACֹֹ_Sources") (part "b4654b650e69147ec39a6b967a45e02"))
    )
    (comp (ref "C125")
      (value "C1005X7R1C104K050BC")
      (footprint "C0402")
      (description "Multilayer Ceramic Capacitors 100nF ±10% 16V X7R SMD 0402")
      (fields (field (name "VOLTAGE") "16V") (field (name "TOLERANCE") "10%"))
      (libsource (lib "DACֹֹ_Sources") (part "b4654b650e69147ec39a6b967a45e02"))
    )
    (comp (ref "C126")
      (value "C1005X7R1C104K050BC")
      (footprint "C0402")
      (description "Multilayer Ceramic Capacitors 100nF ±10% 16V X7R SMD 0402")
      (fields (field (name "VOLTAGE") "16V") (field (name "TOLERANCE") "10%"))
      (libsource (lib "DACֹֹ_Sources") (part "b4654b650e69147ec39a6b967a45e02"))
    )
    (comp (ref "C127")
      (value "C1005X7R1C104K050BC")
      (footprint "C0402")
      (description "Multilayer Ceramic Capacitors 100nF ±10% 16V X7R SMD 0402")
      (fields (field (name "VOLTAGE") "16V") (field (name "TOLERANCE") "10%"))
      (libsource (lib "DACֹֹ_Sources") (part "b4654b650e69147ec39a6b967a45e02"))
    )
    (comp (ref "C128")
      (value "C1005X7R1C104K050BC")
      (footprint "C0402")
      (description "Multilayer Ceramic Capacitors 100nF ±10% 16V X7R SMD 0402")
      (fields (field (name "VOLTAGE") "16V") (field (name "TOLERANCE") "10%"))
      (libsource (lib "DACֹֹ_Sources") (part "b4654b650e69147ec39a6b967a45e02"))
    )
    (comp (ref "C129")
      (value "C1005X7R1C104K050BC")
      (footprint "C0402")
      (description "Multilayer Ceramic Capacitors 100nF ±10% 16V X7R SMD 0402")
      (fields (field (name "VOLTAGE") "16V") (field (name "TOLERANCE") "10%"))
      (libsource (lib "DACֹֹ_Sources") (part "b4654b650e69147ec39a6b967a45e02"))
    )
    (comp (ref "C130")
      (value "C1005X7R1C104K050BC")
      (footprint "C0402")
      (description "Multilayer Ceramic Capacitors 100nF ±10% 16V X7R SMD 0402")
      (fields (field (name "VOLTAGE") "16V") (field (name "TOLERANCE") "10%"))
      (libsource (lib "DACֹֹ_Sources") (part "b4654b650e69147ec39a6b967a45e02"))
    )
    (comp (ref "C131")
      (value "CL31B475KPHNNNE")
      (footprint "C1206")
      (description "Cap Ceramic 4.7uF 10V X7R ±10% SMD 1206 +125°C Embossed T/R")
      (fields (field (name "TOLERANCE") "10%") (field (name "VOLTAGE") "10V"))
      (libsource (lib "DACֹֹ_Sources") (part "b4654b650e69147ec39a6b967a45e02"))
    )
    (comp (ref "C132")
      (value "CL31B475KPHNNNE")
      (footprint "C1206")
      (description "Cap Ceramic 4.7uF 10V X7R ±10% SMD 1206 +125°C Embossed T/R")
      (fields (field (name "TOLERANCE") "10%") (field (name "VOLTAGE") "10V"))
      (libsource (lib "DACֹֹ_Sources") (part "b4654b650e69147ec39a6b967a45e02"))
    )
    (comp (ref "C133")
      (value "C1005X7R1C104K050BC")
      (footprint "C0402")
      (description "Multilayer Ceramic Capacitors 100nF ±10% 16V X7R SMD 0402")
      (fields (field (name "VOLTAGE") "16V") (field (name "TOLERANCE") "10%"))
      (libsource (lib "DACֹֹ_Sources") (part "b4654b650e69147ec39a6b967a45e02"))
    )
    (comp (ref "C134")
      (value "C1005X7R1C104K050BC")
      (footprint "C0402")
      (description "Multilayer Ceramic Capacitors 100nF ±10% 16V X7R SMD 0402")
      (fields (field (name "VOLTAGE") "16V") (field (name "TOLERANCE") "10%"))
      (libsource (lib "DACֹֹ_Sources") (part "b4654b650e69147ec39a6b967a45e02"))
    )
    (comp (ref "C135")
      (value "C1005X7R1C104K050BC")
      (footprint "C0402")
      (description "Multilayer Ceramic Capacitors 100nF ±10% 16V X7R SMD 0402")
      (fields (field (name "VOLTAGE") "16V") (field (name "TOLERANCE") "10%"))
      (libsource (lib "DACֹֹ_Sources") (part "b4654b650e69147ec39a6b967a45e02"))
    )
    (comp (ref "C136")
      (value "C1005X7R1C104K050BC")
      (footprint "C0402")
      (description "Multilayer Ceramic Capacitors 100nF ±10% 16V X7R SMD 0402")
      (fields (field (name "VOLTAGE") "16V") (field (name "TOLERANCE") "10%"))
      (libsource (lib "DACֹֹ_Sources") (part "b4654b650e69147ec39a6b967a45e02"))
    )
    (comp (ref "C137")
      (value "C1005X7R1C104K050BC")
      (footprint "C0402")
      (description "Multilayer Ceramic Capacitors 100nF ±10% 16V X7R SMD 0402")
      (fields (field (name "VOLTAGE") "16V") (field (name "TOLERANCE") "10%"))
      (libsource (lib "DACֹֹ_Sources") (part "b4654b650e69147ec39a6b967a45e02"))
    )
    (comp (ref "C138")
      (value "C1005X7R1C104K050BC")
      (footprint "C0402")
      (description "Multilayer Ceramic Capacitors 100nF ±10% 16V X7R SMD 0402")
      (fields (field (name "VOLTAGE") "16V") (field (name "TOLERANCE") "10%"))
      (libsource (lib "DACֹֹ_Sources") (part "b4654b650e69147ec39a6b967a45e02"))
    )
    (comp (ref "C139")
      (value "C1005X7R1C104K050BC")
      (footprint "C0402")
      (description "Multilayer Ceramic Capacitors 100nF ±10% 16V X7R SMD 0402")
      (fields (field (name "VOLTAGE") "16V") (field (name "TOLERANCE") "10%"))
      (libsource (lib "DACֹֹ_Sources") (part "b4654b650e69147ec39a6b967a45e02"))
    )
    (comp (ref "C140")
      (value "C1005X7R1C104K050BC")
      (footprint "C0402")
      (description "Multilayer Ceramic Capacitors 100nF ±10% 16V X7R SMD 0402")
      (fields (field (name "VOLTAGE") "16V") (field (name "TOLERANCE") "10%"))
      (libsource (lib "DACֹֹ_Sources") (part "b4654b650e69147ec39a6b967a45e02"))
    )
    (comp (ref "C141")
      (value "C1005X7R1E103K050BB")
      (footprint "C0402")
      (description "Multilayer Ceramic Capacitors 10nF ±10% 25V X7R SMD 0402")
      (fields (field (name "TOLERANCE") "10%") (field (name "VOLTAGE") "25V"))
      (libsource (lib "DACֹֹ_Sources") (part "b4654b650e69147ec39a6b967a45e02"))
    )
    (comp (ref "C281")
      (value "C1005X7R1E103K050BB")
      (footprint "C0402")
      (description "Multilayer Ceramic Capacitors 10nF ±10% 25V X7R SMD 0402")
      (fields (field (name "TOLERANCE") "10%") (field (name "VOLTAGE") "25V"))
      (libsource (lib "DACֹֹ_Sources") (part "b4654b650e69147ec39a6b967a45e02"))
    )
    (comp (ref "C282")
      (value "C1005X7R1E103K050BB")
      (footprint "C0402")
      (description "Multilayer Ceramic Capacitors 10nF ±10% 25V X7R SMD 0402")
      (fields (field (name "TOLERANCE") "10%") (field (name "VOLTAGE") "25V"))
      (libsource (lib "DACֹֹ_Sources") (part "b4654b650e69147ec39a6b967a45e02"))
    )
    (comp (ref "C290")
      (value "C1608X7R1C105K080AC")
      (footprint "C0603")
      (description "Multilayer Ceramic Capacitors 1μF ±10% 16V X7R SMD 0603")
      (fields (field (name "VOLTAGE") "16V") (field (name "TOLERANCE") "10%"))
      (libsource (lib "DACֹֹ_Sources") (part "236180d848d6139a670b325ea6854c9"))
    )
    (comp (ref "C291")
      (value "C1005X7R1E103K050BB")
      (footprint "C0402")
      (description "Multilayer Ceramic Capacitors 10nF ±10% 25V X7R SMD 0402")
      (fields (field (name "TOLERANCE") "10%") (field (name "VOLTAGE") "25V"))
      (libsource (lib "DACֹֹ_Sources") (part "b4654b650e69147ec39a6b967a45e02"))
    )
    (comp (ref "C292")
      (value "C1608X7R1C105K080AC")
      (footprint "C0603")
      (description "Multilayer Ceramic Capacitors 1μF ±10% 16V X7R SMD 0603")
      (fields (field (name "VOLTAGE") "16V") (field (name "TOLERANCE") "10%"))
      (libsource (lib "DACֹֹ_Sources") (part "236180d848d6139a670b325ea6854c9"))
    )
    (comp (ref "C293")
      (value "C1005X7R1E103K050BB")
      (footprint "C0402")
      (description "Multilayer Ceramic Capacitors 10nF ±10% 25V X7R SMD 0402")
      (fields (field (name "TOLERANCE") "10%") (field (name "VOLTAGE") "25V"))
      (libsource (lib "DACֹֹ_Sources") (part "b4654b650e69147ec39a6b967a45e02"))
    )
    (comp (ref "C294")
      (value "GRM21BR71A106KE51L")
      (footprint "C0805")
      (fields (field (name "MANUFACTURER") "Murata"))
      (libsource (lib "DACֹֹ_Sources") (part "CAP"))
    )
    (comp (ref "C295")
      (value "C0603C220J5GACTU")
      (footprint "C0603")
      (description "Cap Ceramic 22pF 50V C0G 5% SMD 0603 125°C Paper T/R")
      (fields (field (name "TOLERANCE") "0.05") (field (name "MANUFACTURER") "KEMET"))
      (libsource (lib "DACֹֹ_Sources") (part "b4654b650e69147ec39a6b967a45e02"))
    )
    (comp (ref "C296")
      (value "GRM21BR71A106KE51L")
      (footprint "C0805")
      (fields (field (name "MANUFACTURER") "Murata"))
      (libsource (lib "DACֹֹ_Sources") (part "CAP"))
    )
    (comp (ref "C297")
      (value "C1608X7R1C105K080AC")
      (footprint "C0603")
      (description "Multilayer Ceramic Capacitors 1μF ±10% 16V X7R SMD 0603")
      (fields (field (name "VOLTAGE") "16V") (field (name "TOLERANCE") "10%"))
      (libsource (lib "DACֹֹ_Sources") (part "236180d848d6139a670b325ea6854c9"))
    )
    (comp (ref "C298")
      (value "C1005X7R1C104K050BC")
      (footprint "C0402")
      (description "Multilayer Ceramic Capacitors 100nF ±10% 16V X7R SMD 0402")
      (fields (field (name "VOLTAGE") "16V") (field (name "TOLERANCE") "10%"))
      (libsource (lib "DACֹֹ_Sources") (part "b4654b650e69147ec39a6b967a45e02"))
    )
    (comp (ref "C299")
      (value "GRM21BR71A106KE51L")
      (footprint "C0805")
      (fields (field (name "MANUFACTURER") "Murata"))
      (libsource (lib "DACֹֹ_Sources") (part "CAP"))
    )
    (comp (ref "C300")
      (value "C1608X7R1C105K080AC")
      (footprint "C0603")
      (description "Multilayer Ceramic Capacitors 1μF ±10% 16V X7R SMD 0603")
      (fields (field (name "VOLTAGE") "16V") (field (name "TOLERANCE") "10%"))
      (libsource (lib "DACֹֹ_Sources") (part "236180d848d6139a670b325ea6854c9"))
    )
    (comp (ref "C301")
      (value "C1005X7R1E103K050BB")
      (footprint "C0402")
      (description "Multilayer Ceramic Capacitors 10nF ±10% 25V X7R SMD 0402")
      (fields (field (name "TOLERANCE") "10%") (field (name "VOLTAGE") "25V"))
      (libsource (lib "DACֹֹ_Sources") (part "b4654b650e69147ec39a6b967a45e02"))
    )
    (comp (ref "C302")
      (value "GRM21BR71A106KE51L")
      (footprint "C0805")
      (fields (field (name "MANUFACTURER") "Murata"))
      (libsource (lib "DACֹֹ_Sources") (part "CAP"))
    )
    (comp (ref "C303")
      (value "GRM21BR71A106KE51L")
      (footprint "C0805")
      (fields (field (name "MANUFACTURER") "Murata"))
      (libsource (lib "DACֹֹ_Sources") (part "CAP"))
    )
    (comp (ref "C304")
      (value "C1608X7R1C105K080AC")
      (footprint "C0603")
      (description "Multilayer Ceramic Capacitors 1μF ±10% 16V X7R SMD 0603")
      (fields (field (name "VOLTAGE") "16V") (field (name "TOLERANCE") "10%"))
      (libsource (lib "DACֹֹ_Sources") (part "236180d848d6139a670b325ea6854c9"))
    )
    (comp (ref "C305")
      (value "C1005X7R1C104K050BC")
      (footprint "C0402")
      (description "Multilayer Ceramic Capacitors 100nF ±10% 16V X7R SMD 0402")
      (fields (field (name "VOLTAGE") "16V") (field (name "TOLERANCE") "10%"))
      (libsource (lib "DACֹֹ_Sources") (part "b4654b650e69147ec39a6b967a45e02"))
    )
    (comp (ref "C324")
      (value "GRM21BR71A106KE51L")
      (footprint "C0805")
      (fields (field (name "MANUFACTURER") "Murata"))
      (libsource (lib "DACֹֹ_Sources") (part "CAP"))
    )
    (comp (ref "C325")
      (value "LMK105BJ225KV-F")
      (footprint "C0402")
      (description "None")
      (fields (field (name "TOLERANCE") "10%"))
      (libsource (lib "DACֹֹ_Sources") (part "b4654b650e69147ec39a6b967a45e02"))
    )
    (comp (ref "C326")
      (value "C1608X7R1C105K080AC")
      (footprint "C0603")
      (description "Multilayer Ceramic Capacitors 1μF ±10% 16V X7R SMD 0603")
      (fields (field (name "VOLTAGE") "16V") (field (name "TOLERANCE") "10%"))
      (libsource (lib "DACֹֹ_Sources") (part "236180d848d6139a670b325ea6854c9"))
    )
    (comp (ref "C327")
      (value "C1005X7R1E103K050BB")
      (footprint "C0402")
      (description "Multilayer Ceramic Capacitors 10nF ±10% 25V X7R SMD 0402")
      (fields (field (name "TOLERANCE") "10%") (field (name "VOLTAGE") "25V"))
      (libsource (lib "DACֹֹ_Sources") (part "b4654b650e69147ec39a6b967a45e02"))
    )
    (comp (ref "C328")
      (value "C1608X7R1C105K080AC")
      (footprint "C0603")
      (description "Multilayer Ceramic Capacitors 1μF ±10% 16V X7R SMD 0603")
      (fields (field (name "VOLTAGE") "16V") (field (name "TOLERANCE") "10%"))
      (libsource (lib "DACֹֹ_Sources") (part "236180d848d6139a670b325ea6854c9"))
    )
    (comp (ref "C329")
      (value "C1005X7R1E103K050BB")
      (footprint "C0402")
      (description "Multilayer Ceramic Capacitors 10nF ±10% 25V X7R SMD 0402")
      (fields (field (name "TOLERANCE") "10%") (field (name "VOLTAGE") "25V"))
      (libsource (lib "DACֹֹ_Sources") (part "b4654b650e69147ec39a6b967a45e02"))
    )
    (comp (ref "C330")
      (value "GRM21BR71A106KE51L")
      (footprint "C0805")
      (fields (field (name "MANUFACTURER") "Murata"))
      (libsource (lib "DACֹֹ_Sources") (part "CAP"))
    )
    (comp (ref "C331")
      (value "GRM21BR71A106KE51L")
      (footprint "C0805")
      (fields (field (name "MANUFACTURER") "Murata"))
      (libsource (lib "DACֹֹ_Sources") (part "CAP"))
    )
    (comp (ref "C332")
      (value "LMK105BJ225KV-F")
      (footprint "C0402")
      (description "None")
      (fields (field (name "TOLERANCE") "10%"))
      (libsource (lib "DACֹֹ_Sources") (part "b4654b650e69147ec39a6b967a45e02"))
    )
    (comp (ref "D2")
      (value "LTST-C170TBKT")
      (footprint "FP-LTST-C170TBKT-MFG")
      (description "LED BLUE CLEAR SMD")
      (libsource (lib "DACֹֹ_Sources") (part "8706943c75ba83719d021d2fdc84c58"))
    )
    (comp (ref "FB7")
      (value "FBMJ3216HM600-T")
      (footprint "BEADC3216X130N")
      (description "Ind Chip Bead 60Ohm 25% Ferrite 4A 1206 T/R")
      (libsource (lib "DACֹֹ_Sources") (part "FBMJ3216HM600-T"))
    )
    (comp (ref "FB8")
      (value "NFM31PC276B0J3L")
      (footprint "FP-NFM31-0_2-MFG")
      (fields (field (name "VOLTAGE") "6.3V") (field (name "TOLERANCE") "20%"))
      (libsource (lib "DACֹֹ_Sources") (part "968ca41a07abfef6fd4f7114a56c54f"))
    )
    (comp (ref "FB9")
      (value "NFM31PC276B0J3L")
      (footprint "FP-NFM31-0_2-MFG")
      (fields (field (name "VOLTAGE") "6.3V") (field (name "TOLERANCE") "20%"))
      (libsource (lib "DACֹֹ_Sources") (part "968ca41a07abfef6fd4f7114a56c54f"))
    )
    (comp (ref "FB10")
      (value "BLM41PG102SN1L")
      (footprint "BLM41")
      (description "Ferrite Bead, 1806, 1000Ω @ 100MHz, 25%, 0.09Ω, 1.5A")
      (fields (field (name "TOLERANCE") "25%"))
      (libsource (lib "DACֹֹ_Sources") (part "5f30dd21d616792df468990f7003faa"))
    )
    (comp (ref "FB12")
      (value "BLM41PG102SN1L")
      (footprint "BLM41")
      (description "Ferrite Bead, 1806, 1000Ω @ 100MHz, 25%, 0.09Ω, 1.5A")
      (fields (field (name "TOLERANCE") "25%"))
      (libsource (lib "DACֹֹ_Sources") (part "5f30dd21d616792df468990f7003faa"))
    )
    (comp (ref "FB13")
      (value "BLM41PG102SN1L")
      (footprint "BLM41")
      (description "Ferrite Bead, 1806, 1000Ω @ 100MHz, 25%, 0.09Ω, 1.5A")
      (fields (field (name "TOLERANCE") "25%"))
      (libsource (lib "DACֹֹ_Sources") (part "5f30dd21d616792df468990f7003faa"))
    )
    (comp (ref "FB14")
      (value "NFM31PC276B0J3L")
      (footprint "FP-NFM31-0_2-MFG")
      (fields (field (name "VOLTAGE") "6.3V") (field (name "TOLERANCE") "20%"))
      (libsource (lib "DACֹֹ_Sources") (part "968ca41a07abfef6fd4f7114a56c54f"))
    )
    (comp (ref "FB15")
      (value "BLM41PG102SN1L")
      (footprint "BLM41")
      (description "Ferrite Bead, 1806, 1000Ω @ 100MHz, 25%, 0.09Ω, 1.5A")
      (fields (field (name "TOLERANCE") "25%"))
      (libsource (lib "DACֹֹ_Sources") (part "5f30dd21d616792df468990f7003faa"))
    )
    (comp (ref "FB16")
      (value "BLM41PG102SN1L")
      (footprint "BLM41")
      (description "Ferrite Bead, 1806, 1000Ω @ 100MHz, 25%, 0.09Ω, 1.5A")
      (fields (field (name "TOLERANCE") "25%"))
      (libsource (lib "DACֹֹ_Sources") (part "5f30dd21d616792df468990f7003faa"))
    )
    (comp (ref "FB24")
      (value "NFM31PC276B0J3L")
      (footprint "FP-NFM31-0_2-MFG")
      (fields (field (name "VOLTAGE") "6.3V") (field (name "TOLERANCE") "20%"))
      (libsource (lib "DACֹֹ_Sources") (part "968ca41a07abfef6fd4f7114a56c54f"))
    )
    (comp (ref "FB26")
      (value "BLM41PG102SN1L")
      (footprint "BLM41")
      (description "Ferrite Bead, 1806, 1000Ω @ 100MHz, 25%, 0.09Ω, 1.5A")
      (fields (field (name "TOLERANCE") "25%"))
      (libsource (lib "DACֹֹ_Sources") (part "5f30dd21d616792df468990f7003faa"))
    )
    (comp (ref "FB27")
      (value "BLM41PG102SN1L")
      (footprint "BLM41")
      (description "Ferrite Bead, 1806, 1000Ω @ 100MHz, 25%, 0.09Ω, 1.5A")
      (fields (field (name "TOLERANCE") "25%"))
      (libsource (lib "DACֹֹ_Sources") (part "5f30dd21d616792df468990f7003faa"))
    )
    (comp (ref "J6")
      (value "RAPC722X")
      (footprint "SWITCH-RAPC712X-3_V")
      (description "Power Jack, 5 A, 3-Pin THD, RoHS, Bulk")
      (fields (field (name "MANUFACTURER") "Switchcraft"))
      (libsource (lib "DACֹֹ_Sources") (part "SWITCH-RAPC712X-3"))
    )
    (comp (ref "L1")
      (value "LPS3015-222MR")
      (footprint "lps3015")
      (libsource (lib "DACֹֹ_Sources") (part "Component_1"))
    )
    (comp (ref "L2")
      (value "LPS3015-222MR")
      (footprint "lps3015")
      (libsource (lib "DACֹֹ_Sources") (part "Component_1"))
    )
    (comp (ref "L3")
      (value "LPS3015-222MR")
      (footprint "lps3015")
      (libsource (lib "DACֹֹ_Sources") (part "Component_1"))
    )
    (comp (ref "L4")
      (value "LPS3015-222MR")
      (footprint "lps3015")
      (libsource (lib "DACֹֹ_Sources") (part "Component_1"))
    )
    (comp (ref "L5")
      (value "LPS3015-222MR")
      (footprint "lps3015")
      (libsource (lib "DACֹֹ_Sources") (part "Component_1"))
    )
    (comp (ref "L70")
      (value "LPS3015-222MR")
      (footprint "lps3015")
      (libsource (lib "DACֹֹ_Sources") (part "Component_1"))
    )
    (comp (ref "Q1")
      (value "CSD18532Q5BT")
      (footprint "FP-DNK0008A-MFG")
      (description "MOSFET N-CH 60V 100A 8VSON")
      (libsource (lib "DACֹֹ_Sources") (part "7382af88e928fdc71488234cfaaf11c"))
    )
    (comp (ref "R32")
      (value "750K 5% 0402(1005)")
      (footprint "R0402")
      (description "750K 0.063W 5% 0402 (1005 Metric)  SMD")
      (fields (field (name "TOLERANCE") "5 %") (field (name "POWER") "0.063 W"))
      (libsource (lib "DACֹֹ_Sources") (part "RES"))
    )
    (comp (ref "R33")
      (value "ERJ-3EKF3092V")
      (footprint "R0603")
      (fields (field (name "MANUFACTURER") "Panasonic"))
      (libsource (lib "DACֹֹ_Sources") (part "RES"))
    )
    (comp (ref "R34")
      (value "ERJ3EKF1002V")
      (footprint "R0603")
      (description "Chip Resistor, 10 KOhm, +/- 1%, 0.1 W, -55 to 155 degC, 0603 (1608 Metric), RoHS, Tape and Reel")
      (fields (field (name "TOLERANCE") "1%") (field (name "MANUFACTURER") "Panasonic"))
      (libsource (lib "DACֹֹ_Sources") (part "RES-2"))
    )
    (comp (ref "R35")
      (value "ERJ3EKF1002V")
      (footprint "R0603")
      (description "Chip Resistor, 10 KOhm, +/- 1%, 0.1 W, -55 to 155 degC, 0603 (1608 Metric), RoHS, Tape and Reel")
      (fields (field (name "TOLERANCE") "1%") (field (name "MANUFACTURER") "Panasonic"))
      (libsource (lib "DACֹֹ_Sources") (part "RES-2"))
    )
    (comp (ref "R36")
      (value "RC0402FR-07150KL")
      (footprint "R0402")
      (description "RES 150K OHM 1% 1/16W 0402")
      (fields (field (name "TOLERANCE") "1%"))
      (libsource (lib "DACֹֹ_Sources") (part "1029c3af85768c4190bb7ad29bc67b5"))
    )
    (comp (ref "R37")
      (value "CRCW0603750KFKEA")
      (footprint "R0603")
      (fields (field (name "MANUFACTURER") "Vishay Dale"))
      (libsource (lib "DACֹֹ_Sources") (part "RES"))
    )
    (comp (ref "R38")
      (value "RC0603FR-07150KL")
      (footprint "R0603")
      (fields (field (name "TOLERANCE") "1%"))
      (libsource (lib "DACֹֹ_Sources") (part "1029c3af85768c4190bb7ad29bc67b5"))
    )
    (comp (ref "R40")
      (value "RC0402FR-07174KL")
      (footprint "R0402")
      (fields (field (name "MANUFACTURER") "Yageo"))
      (libsource (lib "Simulation Generic Components") (part "RES"))
    )
    (comp (ref "R41")
      (value "ERJ-3EKF1823V")
      (footprint "R0603")
      (fields (field (name "MANUFACTURER") "Panasonic"))
      (libsource (lib "DACֹֹ_Sources") (part "RES"))
    )
    (comp (ref "R42")
      (value "ERJ2RKF3303X")
      (footprint "R0402")
      (fields (field (name "MANUFACTURER") "Panasonic"))
      (libsource (lib "Simulation Generic Components") (part "RES"))
    )
    (comp (ref "R43")
      (value "RC0402FR-07174KL")
      (footprint "R0402")
      (fields (field (name "MANUFACTURER") "Yageo"))
      (libsource (lib "Simulation Generic Components") (part "RES"))
    )
    (comp (ref "R44")
      (value "ERJ2RKF3303X")
      (footprint "R0402")
      (fields (field (name "MANUFACTURER") "Panasonic"))
      (libsource (lib "Simulation Generic Components") (part "RES"))
    )
    (comp (ref "R51")
      (value "CRCW0603750KFKEA")
      (footprint "R0603")
      (fields (field (name "MANUFACTURER") "Vishay Dale"))
      (libsource (lib "DACֹֹ_Sources") (part "RES"))
    )
    (comp (ref "R52")
      (value "RC0603FR-07150KL")
      (footprint "R0603")
      (fields (field (name "TOLERANCE") "1%"))
      (libsource (lib "DACֹֹ_Sources") (part "1029c3af85768c4190bb7ad29bc67b5"))
    )
    (comp (ref "R54")
      (value "RC0402FR-07174KL")
      (footprint "R0402")
      (fields (field (name "MANUFACTURER") "Yageo"))
      (libsource (lib "Simulation Generic Components") (part "RES"))
    )
    (comp (ref "R55")
      (value "ERJ-3EKF1823V")
      (footprint "R0603")
      (fields (field (name "MANUFACTURER") "Panasonic"))
      (libsource (lib "DACֹֹ_Sources") (part "RES"))
    )
    (comp (ref "R56")
      (value "ERJ2RKF3303X")
      (footprint "R0402")
      (fields (field (name "MANUFACTURER") "Panasonic"))
      (libsource (lib "Simulation Generic Components") (part "RES"))
    )
    (comp (ref "R57")
      (value "RC0402FR-07174KL")
      (footprint "R0402")
      (fields (field (name "MANUFACTURER") "Yageo"))
      (libsource (lib "Simulation Generic Components") (part "RES"))
    )
    (comp (ref "R58")
      (value "ERJ2RKF3303X")
      (footprint "R0402")
      (fields (field (name "MANUFACTURER") "Panasonic"))
      (libsource (lib "Simulation Generic Components") (part "RES"))
    )
    (comp (ref "R105")
      (value "AF0603FR-07270KL")
      (footprint "R0603")
      (description "Anti-Sulfurated Chip Resistors Automotive Grade 270kΩ 1% 100ppm/°C 0603")
      (fields (field (name "TOLERANCE") "1%"))
      (libsource (lib "Simulation Generic Components") (part "1029c3af85768c4190bb7ad29bc67b5"))
    )
    (comp (ref "R106")
      (value "RC0402FR-07174KL")
      (footprint "R0402")
      (fields (field (name "MANUFACTURER") "Yageo"))
      (libsource (lib "Simulation Generic Components") (part "RES"))
    )
    (comp (ref "R107")
      (value "750K 5% 0402(1005)")
      (footprint "R0402")
      (description "750K 0.063W 5% 0402 (1005 Metric)  SMD")
      (fields (field (name "TOLERANCE") "5 %") (field (name "POWER") "0.063 W"))
      (libsource (lib "DACֹֹ_Sources") (part "RES"))
    )
    (comp (ref "R108")
      (value "RC0402FR-07150KL")
      (footprint "R0402")
      (description "RES 150K OHM 1% 1/16W 0402")
      (fields (field (name "TOLERANCE") "1%"))
      (libsource (lib "DACֹֹ_Sources") (part "1029c3af85768c4190bb7ad29bc67b5"))
    )
    (comp (ref "R109")
      (value "ERJ-3EKF3092V")
      (footprint "R0603")
      (fields (field (name "MANUFACTURER") "Panasonic"))
      (libsource (lib "DACֹֹ_Sources") (part "RES"))
    )
    (comp (ref "R110")
      (value "ERJ3EKF1002V")
      (footprint "R0603")
      (description "Chip Resistor, 10 KOhm, +/- 1%, 0.1 W, -55 to 155 degC, 0603 (1608 Metric), RoHS, Tape and Reel")
      (fields (field (name "TOLERANCE") "1%") (field (name "MANUFACTURER") "Panasonic"))
      (libsource (lib "DACֹֹ_Sources") (part "RES-2"))
    )
    (comp (ref "R122")
      (value "ERJ2RKF3303X")
      (footprint "R0402")
      (fields (field (name "MANUFACTURER") "Panasonic"))
      (libsource (lib "Simulation Generic Components") (part "RES"))
    )
    (comp (ref "R123")
      (value "AF0603FR-07270KL")
      (footprint "R0603")
      (description "Anti-Sulfurated Chip Resistors Automotive Grade 270kΩ 1% 100ppm/°C 0603")
      (fields (field (name "TOLERANCE") "1%"))
      (libsource (lib "Simulation Generic Components") (part "1029c3af85768c4190bb7ad29bc67b5"))
    )
    (comp (ref "R124")
      (value "RC0402FR-07174KL")
      (footprint "R0402")
      (fields (field (name "MANUFACTURER") "Yageo"))
      (libsource (lib "Simulation Generic Components") (part "RES"))
    )
    (comp (ref "R125")
      (value "ERJ2RKF3303X")
      (footprint "R0402")
      (fields (field (name "MANUFACTURER") "Panasonic"))
      (libsource (lib "Simulation Generic Components") (part "RES"))
    )
    (comp (ref "U8")
      (value "TPS62290DRVR")
      (footprint "FP-DRV0006A-IPC_A")
      (description "IC REG BUCK ADJUSTABLE 1A 6SON")
      (libsource (lib "DACֹֹ_Sources") (part "e18bba32e79127f802312c6d0d2e879"))
    )
    (comp (ref "U9")
      (value "TPS7A8001DRBR")
      (footprint "DRB0008A_V")
      (fields (field (name "MANUFACTURER") "Texas Instruments"))
      (libsource (lib "DACֹֹ_Sources") (part "TI-TPS7A8X01DRB8-1750X1500TP"))
    )
    (comp (ref "U10")
      (value "TPS79633QDCQRQ1")
      (footprint "DCQ0006A")
      (fields (field (name "MANUFACTURER") "Texas Instruments") (field (name "PARTNUMBER") "TPS79633DCQ"))
      (libsource (lib "DACֹֹ_Sources") (part "TI-TPS7XXXXXXXX"))
    )
    (comp (ref "U11")
      (value "TPS62420DRCR")
      (footprint "DRC0010G")
      (fields (field (name "MANUFACTURER") "Texas Instruments"))
      (libsource (lib "DACֹֹ_Sources") (part "TI-TPS62420DRC10-2400X1650TP"))
    )
    (comp (ref "U12")
      (value "TPS71701DCKR")
      (footprint "DCK")
      (fields (field (name "MANUFACTURER") "Texas Instruments"))
      (libsource (lib "Simulation Generic Components") (part "TI-TPS7XX01-5"))
    )
    (comp (ref "U13")
      (value "TPS71701DCKR")
      (footprint "DCK")
      (fields (field (name "MANUFACTURER") "Texas Instruments"))
      (libsource (lib "Simulation Generic Components") (part "TI-TPS7XX01-5"))
    )
    (comp (ref "U14")
      (value "TPS2400DBVT")
      (footprint "DBV0005A")
      (description "5.5-V over voltage protection controller with 100-V input transient protection 5-SOT-23 -40 to 85")
      (fields
        (field (name "MF") "Texas Instruments")
        (field (name "BUYPART") "https://www.snapeda.com/parts/TPS2400DBVT/Texas%20Instruments/view-part/425327/?ref=eda")
      )
      (libsource (lib "DACֹֹ_Sources") (part "TPS2400DBVT"))
    )
    (comp (ref "U15")
      (value "TPS79633QDCQRQ1")
      (footprint "DCQ0006A")
      (fields (field (name "MANUFACTURER") "Texas Instruments") (field (name "PARTNUMBER") "TPS79633DCQ"))
      (libsource (lib "DACֹֹ_Sources") (part "TI-TPS7XXXXXXXX"))
    )
    (comp (ref "U16")
      (value "TPS62420DRCR")
      (footprint "DRC0010G")
      (fields (field (name "MANUFACTURER") "Texas Instruments"))
      (libsource (lib "DACֹֹ_Sources") (part "TI-TPS62420DRC10-2400X1650TP"))
    )
    (comp (ref "U17")
      (value "TPS71701DCKR")
      (footprint "DCK")
      (fields (field (name "MANUFACTURER") "Texas Instruments"))
      (libsource (lib "Simulation Generic Components") (part "TI-TPS7XX01-5"))
    )
    (comp (ref "U18")
      (value "TPS71701DCKR")
      (footprint "DCK")
      (fields (field (name "MANUFACTURER") "Texas Instruments"))
      (libsource (lib "Simulation Generic Components") (part "TI-TPS7XX01-5"))
    )
    (comp (ref "U19")
      (value "ADP1706ARDZ-3.3-R7")
      (footprint "ADI-RD-8-2_M")
      (fields (field (name "MANUFACTURER") "Analog Devices"))
      (libsource (lib "DACֹֹ_Sources") (part "ADI-ADP1706-RD-8-2"))
    )
    (comp (ref "U20")
      (value "ADP1706ARDZ-1.8-R7")
      (footprint "ADI-RD-8-2_M")
      (fields (field (name "MANUFACTURER") "Analog Devices"))
      (libsource (lib "DACֹֹ_Sources") (part "ADI-ADP1706-RD-8-2"))
    )
    (comp (ref "U21")
      (value "ADP1706ARDZ-1.8-R7")
      (footprint "ADI-RD-8-2_M")
      (fields (field (name "MANUFACTURER") "Analog Devices"))
      (libsource (lib "DACֹֹ_Sources") (part "ADI-ADP1706-RD-8-2"))
    )
    (comp (ref "U32")
      (value "TPS62290DRVR")
      (footprint "FP-DRV0006A-IPC_A")
      (description "IC REG BUCK ADJUSTABLE 1A 6SON")
      (libsource (lib "DACֹֹ_Sources") (part "e18bba32e79127f802312c6d0d2e879"))
    )
    (comp (ref "U33")
      (value "TPS7A8001DRBR")
      (footprint "DRB0008A_V")
      (fields (field (name "MANUFACTURER") "Texas Instruments"))
      (libsource (lib "DACֹֹ_Sources") (part "TI-TPS7A8X01DRB8-1750X1500TP"))
    )
    (comp (ref "U34")
      (value "TPS71701DCKR")
      (footprint "DCK")
      (fields (field (name "MANUFACTURER") "Texas Instruments"))
      (libsource (lib "Simulation Generic Components") (part "TI-TPS7XX01-5"))
    )
    (comp (ref "U35")
      (value "TPS71701DCKR")
      (footprint "DCK")
      (fields (field (name "MANUFACTURER") "Texas Instruments"))
      (libsource (lib "Simulation Generic Components") (part "TI-TPS7XX01-5"))
    )
  )
  (nets
    (net (code "1") (name "/1.2VCLK_DAC1") (class "Default")
      (node (ref "C73") (pin "2") (pinfunction "2_2") (pintype "passive"))
      (node (ref "C74") (pin "1") (pinfunction "1_1") (pintype "passive"))
      (node (ref "C76") (pin "2") (pinfunction "2_2") (pintype "passive"))
      (node (ref "FB13") (pin "2") (pinfunction "2_2") (pintype "passive"))
    )
    (net (code "2") (name "/1.2VCLK_DAC2") (class "Default")
      (node (ref "C108") (pin "2") (pinfunction "2_2") (pintype "passive"))
      (node (ref "C109") (pin "1") (pinfunction "1_1") (pintype "passive"))
      (node (ref "C111") (pin "2") (pinfunction "2_2") (pintype "passive"))
      (node (ref "FB16") (pin "2") (pinfunction "2_2") (pintype "passive"))
    )
    (net (code "3") (name "/1.2VDAC1") (class "Default")
      (node (ref "C66") (pin "2") (pinfunction "2_2") (pintype "passive"))
      (node (ref "C67") (pin "1") (pinfunction "1_1") (pintype "passive"))
      (node (ref "C69") (pin "2") (pinfunction "2_2") (pintype "passive"))
      (node (ref "FB10") (pin "2") (pinfunction "2_2") (pintype "passive"))
    )
    (net (code "4") (name "/1.2VDAC2") (class "Default")
      (node (ref "C101") (pin "2") (pinfunction "2_2") (pintype "passive"))
      (node (ref "C102") (pin "1") (pinfunction "1_1") (pintype "passive"))
      (node (ref "C104") (pin "2") (pinfunction "2_2") (pintype "passive"))
      (node (ref "FB15") (pin "2") (pinfunction "2_2") (pintype "passive"))
    )
    (net (code "5") (name "/1.2VDIGI_DAC1") (class "Default")
      (node (ref "C292") (pin "2") (pinfunction "2_2") (pintype "passive"))
      (node (ref "C293") (pin "1") (pinfunction "1_1") (pintype "passive"))
      (node (ref "C324") (pin "2") (pinfunction "2_2") (pintype "passive"))
      (node (ref "FB26") (pin "2") (pinfunction "2_2") (pintype "passive"))
    )
    (net (code "6") (name "/1.2VDIGI_DAC2") (class "Default")
      (node (ref "C328") (pin "2") (pinfunction "2_2") (pintype "passive"))
      (node (ref "C329") (pin "1") (pinfunction "1_1") (pintype "passive"))
      (node (ref "C331") (pin "2") (pinfunction "2_2") (pintype "passive"))
      (node (ref "FB27") (pin "2") (pinfunction "2_2") (pintype "passive"))
    )
    (net (code "7") (name "/1.8V_AVDD") (class "Default")
      (node (ref "C118") (pin "1") (pinfunction "1_1") (pintype "passive"))
      (node (ref "C119") (pin "1") (pinfunction "1_1") (pintype "passive"))
      (node (ref "C120") (pin "1") (pinfunction "1_1") (pintype "passive"))
      (node (ref "C122") (pin "1") (pinfunction "1_1") (pintype "passive"))
      (node (ref "C124") (pin "1") (pinfunction "1_1") (pintype "passive"))
      (node (ref "C125") (pin "1") (pinfunction "1_1") (pintype "passive"))
      (node (ref "C126") (pin "1") (pinfunction "1_1") (pintype "passive"))
      (node (ref "C127") (pin "1") (pinfunction "1_1") (pintype "passive"))
      (node (ref "C128") (pin "1") (pinfunction "1_1") (pintype "passive"))
      (node (ref "C129") (pin "1") (pinfunction "1_1") (pintype "passive"))
      (node (ref "C130") (pin "1") (pinfunction "1_1") (pintype "passive"))
      (node (ref "U20") (pin "5") (pinfunction "OUT_5") (pintype "power_in"))
      (node (ref "U20") (pin "6") (pinfunction "OUT_6") (pintype "power_in"))
      (node (ref "U20") (pin "7") (pinfunction "SENSE_7") (pintype "input"))
    )
    (net (code "8") (name "/1.8V_DRVDD") (class "Default")
      (node (ref "C116") (pin "1") (pinfunction "1_1") (pintype "passive"))
      (node (ref "C117") (pin "1") (pinfunction "1_1") (pintype "passive"))
      (node (ref "C132") (pin "1") (pinfunction "1_1") (pintype "passive"))
      (node (ref "C133") (pin "1") (pinfunction "1_1") (pintype "passive"))
      (node (ref "C134") (pin "1") (pinfunction "1_1") (pintype "passive"))
      (node (ref "C135") (pin "1") (pinfunction "1_1") (pintype "passive"))
      (node (ref "U21") (pin "5") (pinfunction "OUT_5") (pintype "power_in"))
      (node (ref "U21") (pin "6") (pinfunction "OUT_6") (pintype "power_in"))
      (node (ref "U21") (pin "7") (pinfunction "SENSE_7") (pintype "input"))
    )
    (net (code "9") (name "/3.3VA_DAC1") (class "Default")
      (node (ref "C53") (pin "2") (pinfunction "2_2") (pintype "passive"))
      (node (ref "C54") (pin "1") (pinfunction "1_1") (pintype "passive"))
      (node (ref "C56") (pin "2") (pinfunction "2_2") (pintype "passive"))
      (node (ref "U10") (pin "4") (pinfunction "OUT_4") (pintype "power_in"))
    )
    (net (code "10") (name "/3.3VA_DAC2") (class "Default")
      (node (ref "C88") (pin "2") (pinfunction "2_2") (pintype "passive"))
      (node (ref "C89") (pin "1") (pinfunction "1_1") (pintype "passive"))
      (node (ref "C91") (pin "2") (pinfunction "2_2") (pintype "passive"))
      (node (ref "U15") (pin "4") (pinfunction "OUT_4") (pintype "power_in"))
    )
    (net (code "11") (name "/3.3VCLK") (class "Default")
      (node (ref "C35") (pin "2") (pinfunction "2_2") (pintype "passive"))
      (node (ref "C36") (pin "1") (pinfunction "1_1") (pintype "passive"))
      (node (ref "C38") (pin "2") (pinfunction "2_2") (pintype "passive"))
      (node (ref "FB12") (pin "1") (pinfunction "1_1") (pintype "passive"))
      (node (ref "R33") (pin "2") (pinfunction "2_2") (pintype "passive"))
      (node (ref "U9") (pin "1") (pinfunction "OUT_1") (pintype "power_in"))
      (node (ref "U9") (pin "2") (pinfunction "OUT_2") (pintype "power_in"))
    )
    (net (code "12") (name "/3.3V_AVDD") (class "Default")
      (node (ref "C114") (pin "1") (pinfunction "1_1") (pintype "passive"))
      (node (ref "C136") (pin "1") (pinfunction "1_1") (pintype "passive"))
      (node (ref "C137") (pin "1") (pinfunction "1_1") (pintype "passive"))
      (node (ref "C138") (pin "1") (pinfunction "1_1") (pintype "passive"))
      (node (ref "C139") (pin "1") (pinfunction "1_1") (pintype "passive"))
      (node (ref "C140") (pin "1") (pinfunction "1_1") (pintype "passive"))
      (node (ref "U19") (pin "5") (pinfunction "OUT_5") (pintype "power_in"))
      (node (ref "U19") (pin "6") (pinfunction "OUT_6") (pintype "power_in"))
      (node (ref "U19") (pin "7") (pinfunction "SENSE_7") (pintype "input"))
    )
    (net (code "13") (name "/3.3V_LOGIC") (class "Default")
      (node (ref "FB12") (pin "2") (pinfunction "2_2") (pintype "passive"))
    )
    (net (code "14") (name "/6V") (class "Default")
      (node (ref "C113") (pin "1") (pinfunction "1_1") (pintype "passive"))
      (node (ref "C121") (pin "1") (pinfunction "1_1") (pintype "passive"))
      (node (ref "C131") (pin "1") (pinfunction "1_1") (pintype "passive"))
      (node (ref "C296") (pin "2") (pinfunction "2_2") (pintype "passive"))
      (node (ref "C297") (pin "2") (pinfunction "2_2") (pintype "passive"))
      (node (ref "C298") (pin "1") (pinfunction "1_1") (pintype "passive"))
      (node (ref "C40") (pin "2") (pinfunction "2_2") (pintype "passive"))
      (node (ref "C42") (pin "2") (pinfunction "2_2") (pintype "passive"))
      (node (ref "C43") (pin "1") (pinfunction "1_1") (pintype "passive"))
      (node (ref "C45") (pin "2") (pinfunction "2_2") (pintype "passive"))
      (node (ref "C47") (pin "1") (pinfunction "1_1") (pintype "passive"))
      (node (ref "C48") (pin "1") (pinfunction "1_1") (pintype "passive"))
      (node (ref "C57") (pin "2") (pinfunction "2_2") (pintype "passive"))
      (node (ref "C58") (pin "2") (pinfunction "2_2") (pintype "passive"))
      (node (ref "C59") (pin "1") (pinfunction "1_1") (pintype "passive"))
      (node (ref "C60") (pin "1") (pinfunction "1_1") (pintype "passive"))
      (node (ref "C92") (pin "2") (pinfunction "2_2") (pintype "passive"))
      (node (ref "C93") (pin "2") (pinfunction "2_2") (pintype "passive"))
      (node (ref "C94") (pin "1") (pinfunction "1_1") (pintype "passive"))
      (node (ref "C95") (pin "1") (pinfunction "1_1") (pintype "passive"))
      (node (ref "FB7") (pin "2") (pinfunction "2_2") (pintype "passive"))
      (node (ref "R34") (pin "2") (pinfunction "2_2") (pintype "passive"))
      (node (ref "U11") (pin "2") (pinfunction "MODE/DATA_2") (pintype "bidirectional"))
      (node (ref "U11") (pin "3") (pinfunction "VIN_3") (pintype "power_in"))
      (node (ref "U11") (pin "7") (pinfunction "EN1_7") (pintype "input"))
      (node (ref "U11") (pin "9") (pinfunction "EN2_9") (pintype "input"))
      (node (ref "U16") (pin "2") (pinfunction "MODE/DATA_2") (pintype "bidirectional"))
      (node (ref "U16") (pin "3") (pinfunction "VIN_3") (pintype "power_in"))
      (node (ref "U16") (pin "7") (pinfunction "EN1_7") (pintype "input"))
      (node (ref "U16") (pin "9") (pinfunction "EN2_9") (pintype "input"))
      (node (ref "U19") (pin "1") (pinfunction "EN_1") (pintype "input"))
      (node (ref "U19") (pin "3") (pinfunction "IN_3") (pintype "power_in"))
      (node (ref "U19") (pin "4") (pinfunction "IN_4") (pintype "power_in"))
      (node (ref "U20") (pin "1") (pinfunction "EN_1") (pintype "input"))
      (node (ref "U20") (pin "3") (pinfunction "IN_3") (pintype "power_in"))
      (node (ref "U20") (pin "4") (pinfunction "IN_4") (pintype "power_in"))
      (node (ref "U21") (pin "1") (pinfunction "EN_1") (pintype "input"))
      (node (ref "U21") (pin "3") (pinfunction "IN_3") (pintype "power_in"))
      (node (ref "U21") (pin "4") (pinfunction "IN_4") (pintype "power_in"))
      (node (ref "U32") (pin "4") (pinfunction "EN_4") (pintype "input"))
      (node (ref "U32") (pin "5") (pinfunction "VIN_5") (pintype "power_in"))
      (node (ref "U8") (pin "4") (pinfunction "EN_4") (pintype "input"))
      (node (ref "U8") (pin "5") (pinfunction "VIN_5") (pintype "power_in"))
    )
    (net (code "16") (name "/DEF1") (class "Default")
      (node (ref "R37") (pin "1") (pinfunction "1_1") (pintype "passive"))
      (node (ref "R38") (pin "2") (pinfunction "2_2") (pintype "passive"))
      (node (ref "U11") (pin "5") (pinfunction "DEF_1_5") (pintype "input"))
    )
    (net (code "17") (name "/DEF2") (class "Default")
      (node (ref "R51") (pin "1") (pinfunction "1_1") (pintype "passive"))
      (node (ref "R52") (pin "2") (pinfunction "2_2") (pintype "passive"))
      (node (ref "U16") (pin "5") (pinfunction "DEF_1_5") (pintype "input"))
    )
    (net (code "18") (name "/VCCO_34") (class "Default")
      (node (ref "C300") (pin "2") (pinfunction "2_2") (pintype "passive"))
      (node (ref "C301") (pin "1") (pinfunction "1_1") (pintype "passive"))
      (node (ref "C303") (pin "2") (pinfunction "2_2") (pintype "passive"))
      (node (ref "R109") (pin "2") (pinfunction "2_2") (pintype "passive"))
      (node (ref "U33") (pin "1") (pinfunction "OUT_1") (pintype "power_in"))
      (node (ref "U33") (pin "2") (pinfunction "OUT_2") (pintype "power_in"))
    )
    (net (code "19") (name "/VIN_HDR") (class "Default")
      (node (ref "C41") (pin "1") (pinfunction "1_1") (pintype "passive"))
      (node (ref "C49") (pin "1") (pinfunction "1_1") (pintype "passive"))
      (node (ref "FB7") (pin "1") (pinfunction "1_1") (pintype "passive"))
      (node (ref "Q1") (pin "1") (pinfunction "S_1") (pintype "passive"))
      (node (ref "Q1") (pin "2") (pinfunction "S_2") (pintype "passive"))
      (node (ref "Q1") (pin "3") (pinfunction "S_3") (pintype "passive"))
    )
    (net (code "20") (name "GND") (class "Default")
      (node (ref "C100") (pin "2") (pinfunction "2_2") (pintype "passive"))
      (node (ref "C101") (pin "1") (pinfunction "1_1") (pintype "passive"))
      (node (ref "C102") (pin "2") (pinfunction "2_2") (pintype "passive"))
      (node (ref "C103") (pin "1") (pinfunction "1_1") (pintype "passive"))
      (node (ref "C104") (pin "1") (pinfunction "1_1") (pintype "passive"))
      (node (ref "C105") (pin "2") (pinfunction "2_2") (pintype "passive"))
      (node (ref "C106") (pin "1") (pinfunction "1_1") (pintype "passive"))
      (node (ref "C107") (pin "2") (pinfunction "2_2") (pintype "passive"))
      (node (ref "C108") (pin "1") (pinfunction "1_1") (pintype "passive"))
      (node (ref "C109") (pin "2") (pinfunction "2_2") (pintype "passive"))
      (node (ref "C110") (pin "1") (pinfunction "1_1") (pintype "passive"))
      (node (ref "C111") (pin "1") (pinfunction "1_1") (pintype "passive"))
      (node (ref "C112") (pin "2") (pinfunction "2_2") (pintype "passive"))
      (node (ref "C113") (pin "2") (pinfunction "2_2") (pintype "passive"))
      (node (ref "C114") (pin "2") (pinfunction "2_2") (pintype "passive"))
      (node (ref "C115") (pin "2") (pinfunction "2_2") (pintype "passive"))
      (node (ref "C116") (pin "2") (pinfunction "2_2") (pintype "passive"))
      (node (ref "C117") (pin "2") (pinfunction "2_2") (pintype "passive"))
      (node (ref "C118") (pin "2") (pinfunction "2_2") (pintype "passive"))
      (node (ref "C119") (pin "2") (pinfunction "2_2") (pintype "passive"))
      (node (ref "C120") (pin "2") (pinfunction "2_2") (pintype "passive"))
      (node (ref "C121") (pin "2") (pinfunction "2_2") (pintype "passive"))
      (node (ref "C122") (pin "2") (pinfunction "2_2") (pintype "passive"))
      (node (ref "C123") (pin "2") (pinfunction "2_2") (pintype "passive"))
      (node (ref "C124") (pin "2") (pinfunction "2_2") (pintype "passive"))
      (node (ref "C125") (pin "2") (pinfunction "2_2") (pintype "passive"))
      (node (ref "C126") (pin "2") (pinfunction "2_2") (pintype "passive"))
      (node (ref "C127") (pin "2") (pinfunction "2_2") (pintype "passive"))
      (node (ref "C128") (pin "2") (pinfunction "2_2") (pintype "passive"))
      (node (ref "C129") (pin "2") (pinfunction "2_2") (pintype "passive"))
      (node (ref "C130") (pin "2") (pinfunction "2_2") (pintype "passive"))
      (node (ref "C131") (pin "2") (pinfunction "2_2") (pintype "passive"))
      (node (ref "C132") (pin "2") (pinfunction "2_2") (pintype "passive"))
      (node (ref "C133") (pin "2") (pinfunction "2_2") (pintype "passive"))
      (node (ref "C134") (pin "2") (pinfunction "2_2") (pintype "passive"))
      (node (ref "C135") (pin "2") (pinfunction "2_2") (pintype "passive"))
      (node (ref "C136") (pin "2") (pinfunction "2_2") (pintype "passive"))
      (node (ref "C137") (pin "2") (pinfunction "2_2") (pintype "passive"))
      (node (ref "C138") (pin "2") (pinfunction "2_2") (pintype "passive"))
      (node (ref "C139") (pin "2") (pinfunction "2_2") (pintype "passive"))
      (node (ref "C140") (pin "2") (pinfunction "2_2") (pintype "passive"))
      (node (ref "C141") (pin "2") (pinfunction "2_2") (pintype "passive"))
      (node (ref "C281") (pin "2") (pinfunction "2_2") (pintype "passive"))
      (node (ref "C282") (pin "2") (pinfunction "2_2") (pintype "passive"))
      (node (ref "C290") (pin "1") (pinfunction "1_1") (pintype "passive"))
      (node (ref "C291") (pin "2") (pinfunction "2_2") (pintype "passive"))
      (node (ref "C292") (pin "1") (pinfunction "1_1") (pintype "passive"))
      (node (ref "C293") (pin "2") (pinfunction "2_2") (pintype "passive"))
      (node (ref "C294") (pin "1") (pinfunction "1_1") (pintype "passive"))
      (node (ref "C296") (pin "1") (pinfunction "1_1") (pintype "passive"))
      (node (ref "C297") (pin "1") (pinfunction "1_1") (pintype "passive"))
      (node (ref "C298") (pin "2") (pinfunction "2_2") (pintype "passive"))
      (node (ref "C299") (pin "1") (pinfunction "1_1") (pintype "passive"))
      (node (ref "C300") (pin "1") (pinfunction "1_1") (pintype "passive"))
      (node (ref "C301") (pin "2") (pinfunction "2_2") (pintype "passive"))
      (node (ref "C302") (pin "1") (pinfunction "1_1") (pintype "passive"))
      (node (ref "C303") (pin "1") (pinfunction "1_1") (pintype "passive"))
      (node (ref "C304") (pin "1") (pinfunction "1_1") (pintype "passive"))
      (node (ref "C305") (pin "2") (pinfunction "2_2") (pintype "passive"))
      (node (ref "C324") (pin "1") (pinfunction "1_1") (pintype "passive"))
      (node (ref "C325") (pin "2") (pinfunction "2_2") (pintype "passive"))
      (node (ref "C326") (pin "1") (pinfunction "1_1") (pintype "passive"))
      (node (ref "C327") (pin "2") (pinfunction "2_2") (pintype "passive"))
      (node (ref "C328") (pin "1") (pinfunction "1_1") (pintype "passive"))
      (node (ref "C329") (pin "2") (pinfunction "2_2") (pintype "passive"))
      (node (ref "C330") (pin "1") (pinfunction "1_1") (pintype "passive"))
      (node (ref "C331") (pin "1") (pinfunction "1_1") (pintype "passive"))
      (node (ref "C332") (pin "2") (pinfunction "2_2") (pintype "passive"))
      (node (ref "C35") (pin "1") (pinfunction "1_1") (pintype "passive"))
      (node (ref "C36") (pin "2") (pinfunction "2_2") (pintype "passive"))
      (node (ref "C37") (pin "1") (pinfunction "1_1") (pintype "passive"))
      (node (ref "C38") (pin "1") (pinfunction "1_1") (pintype "passive"))
      (node (ref "C39") (pin "1") (pinfunction "1_1") (pintype "passive"))
      (node (ref "C40") (pin "1") (pinfunction "1_1") (pintype "passive"))
      (node (ref "C41") (pin "2") (pinfunction "2_2") (pintype "passive"))
      (node (ref "C42") (pin "1") (pinfunction "1_1") (pintype "passive"))
      (node (ref "C43") (pin "2") (pinfunction "2_2") (pintype "passive"))
      (node (ref "C44") (pin "2") (pinfunction "2_2") (pintype "passive"))
      (node (ref "C45") (pin "1") (pinfunction "1_1") (pintype "passive"))
      (node (ref "C46") (pin "1") (pinfunction "1_1") (pintype "passive"))
      (node (ref "C47") (pin "2") (pinfunction "2_2") (pintype "passive"))
      (node (ref "C48") (pin "2") (pinfunction "2_2") (pintype "passive"))
      (node (ref "C49") (pin "2") (pinfunction "2_2") (pintype "passive"))
      (node (ref "C50") (pin "2") (pinfunction "GND_2") (pintype "passive"))
      (node (ref "C51") (pin "2") (pinfunction "2_2") (pintype "passive"))
      (node (ref "C52") (pin "2") (pinfunction "2_2") (pintype "passive"))
      (node (ref "C53") (pin "1") (pinfunction "1_1") (pintype "passive"))
      (node (ref "C54") (pin "2") (pinfunction "2_2") (pintype "passive"))
      (node (ref "C55") (pin "1") (pinfunction "1_1") (pintype "passive"))
      (node (ref "C56") (pin "1") (pinfunction "1_1") (pintype "passive"))
      (node (ref "C57") (pin "1") (pinfunction "1_1") (pintype "passive"))
      (node (ref "C58") (pin "1") (pinfunction "1_1") (pintype "passive"))
      (node (ref "C59") (pin "2") (pinfunction "2_2") (pintype "passive"))
      (node (ref "C60") (pin "2") (pinfunction "2_2") (pintype "passive"))
      (node (ref "C61") (pin "2") (pinfunction "2_2") (pintype "passive"))
      (node (ref "C62") (pin "2") (pinfunction "2_2") (pintype "passive"))
      (node (ref "C63") (pin "1") (pinfunction "1_1") (pintype "passive"))
      (node (ref "C64") (pin "1") (pinfunction "1_1") (pintype "passive"))
      (node (ref "C65") (pin "2") (pinfunction "2_2") (pintype "passive"))
      (node (ref "C66") (pin "1") (pinfunction "1_1") (pintype "passive"))
      (node (ref "C67") (pin "2") (pinfunction "2_2") (pintype "passive"))
      (node (ref "C68") (pin "1") (pinfunction "1_1") (pintype "passive"))
      (node (ref "C69") (pin "1") (pinfunction "1_1") (pintype "passive"))
      (node (ref "C70") (pin "2") (pinfunction "2_2") (pintype "passive"))
      (node (ref "C71") (pin "1") (pinfunction "1_1") (pintype "passive"))
      (node (ref "C72") (pin "2") (pinfunction "2_2") (pintype "passive"))
      (node (ref "C73") (pin "1") (pinfunction "1_1") (pintype "passive"))
      (node (ref "C74") (pin "2") (pinfunction "2_2") (pintype "passive"))
      (node (ref "C75") (pin "1") (pinfunction "1_1") (pintype "passive"))
      (node (ref "C76") (pin "1") (pinfunction "1_1") (pintype "passive"))
      (node (ref "C77") (pin "2") (pinfunction "2_2") (pintype "passive"))
      (node (ref "C85") (pin "2") (pinfunction "GND_2") (pintype "passive"))
      (node (ref "C86") (pin "2") (pinfunction "2_2") (pintype "passive"))
      (node (ref "C87") (pin "2") (pinfunction "2_2") (pintype "passive"))
      (node (ref "C88") (pin "1") (pinfunction "1_1") (pintype "passive"))
      (node (ref "C89") (pin "2") (pinfunction "2_2") (pintype "passive"))
      (node (ref "C90") (pin "1") (pinfunction "1_1") (pintype "passive"))
      (node (ref "C91") (pin "1") (pinfunction "1_1") (pintype "passive"))
      (node (ref "C92") (pin "1") (pinfunction "1_1") (pintype "passive"))
      (node (ref "C93") (pin "1") (pinfunction "1_1") (pintype "passive"))
      (node (ref "C94") (pin "2") (pinfunction "2_2") (pintype "passive"))
      (node (ref "C95") (pin "2") (pinfunction "2_2") (pintype "passive"))
      (node (ref "C96") (pin "2") (pinfunction "2_2") (pintype "passive"))
      (node (ref "C97") (pin "2") (pinfunction "2_2") (pintype "passive"))
      (node (ref "C98") (pin "1") (pinfunction "1_1") (pintype "passive"))
      (node (ref "C99") (pin "1") (pinfunction "1_1") (pintype "passive"))
      (node (ref "D2") (pin "1") (pinfunction "C_1") (pintype "passive"))
      (node (ref "FB14") (pin "2") (pinfunction "GND_2") (pintype "passive"))
      (node (ref "FB24") (pin "2") (pinfunction "GND_2") (pintype "passive"))
      (node (ref "FB8") (pin "2") (pinfunction "GND_2") (pintype "passive"))
      (node (ref "FB9") (pin "2") (pinfunction "GND_2") (pintype "passive"))
      (node (ref "J6") (pin "1") (pinfunction "1_1") (pintype "passive"))
      (node (ref "J6") (pin "2") (pinfunction "2_2") (pintype "passive"))
      (node (ref "R108") (pin "1") (pinfunction "1_1") (pintype "passive"))
      (node (ref "R110") (pin "1") (pinfunction "1_1") (pintype "passive"))
      (node (ref "R122") (pin "1") (pinfunction "1_1") (pintype "passive"))
      (node (ref "R125") (pin "1") (pinfunction "1_1") (pintype "passive"))
      (node (ref "R35") (pin "1") (pinfunction "1_1") (pintype "passive"))
      (node (ref "R36") (pin "1") (pinfunction "1_1") (pintype "passive"))
      (node (ref "R38") (pin "1") (pinfunction "1_1") (pintype "passive"))
      (node (ref "R41") (pin "1") (pinfunction "1_1") (pintype "passive"))
      (node (ref "R42") (pin "1") (pinfunction "1_1") (pintype "passive"))
      (node (ref "R44") (pin "1") (pinfunction "1_1") (pintype "passive"))
      (node (ref "R52") (pin "1") (pinfunction "1_1") (pintype "passive"))
      (node (ref "R55") (pin "1") (pinfunction "1_1") (pintype "passive"))
      (node (ref "R56") (pin "1") (pinfunction "1_1") (pintype "passive"))
      (node (ref "R58") (pin "1") (pinfunction "1_1") (pintype "passive"))
      (node (ref "U10") (pin "3") (pinfunction "GND_3") (pintype "power_in"))
      (node (ref "U10") (pin "6") (pinfunction "GND_6") (pintype "power_in"))
      (node (ref "U11") (pin "11") (pinfunction "PP_11") (pintype "power_in"))
      (node (ref "U11") (pin "8") (pinfunction "GND_8") (pintype "power_in"))
      (node (ref "U12") (pin "2") (pinfunction "GND_2") (pintype "power_in"))
      (node (ref "U13") (pin "2") (pinfunction "GND_2") (pintype "power_in"))
      (node (ref "U14") (pin "2") (pinfunction "GND_2") (pintype "power_in"))
      (node (ref "U15") (pin "3") (pinfunction "GND_3") (pintype "power_in"))
      (node (ref "U15") (pin "6") (pinfunction "GND_6") (pintype "power_in"))
      (node (ref "U16") (pin "11") (pinfunction "PP_11") (pintype "power_in"))
      (node (ref "U16") (pin "8") (pinfunction "GND_8") (pintype "power_in"))
      (node (ref "U17") (pin "2") (pinfunction "GND_2") (pintype "power_in"))
      (node (ref "U18") (pin "2") (pinfunction "GND_2") (pintype "power_in"))
      (node (ref "U19") (pin "2") (pinfunction "GND_2") (pintype "power_in"))
      (node (ref "U19") (pin "9") (pinfunction "EP_9") (pintype "power_in"))
      (node (ref "U20") (pin "2") (pinfunction "GND_2") (pintype "power_in"))
      (node (ref "U20") (pin "9") (pinfunction "EP_9") (pintype "power_in"))
      (node (ref "U21") (pin "2") (pinfunction "GND_2") (pintype "power_in"))
      (node (ref "U21") (pin "9") (pinfunction "EP_9") (pintype "power_in"))
      (node (ref "U32") (pin "2") (pinfunction "MODE_2") (pintype "input"))
      (node (ref "U32") (pin "6") (pinfunction "GND_6") (pintype "power_in"))
      (node (ref "U32") (pin "7") (pinfunction "Exposed_Thermal_Pad_7") (pintype "passive"))
      (node (ref "U33") (pin "4") (pinfunction "GND_4") (pintype "power_in"))
      (node (ref "U33") (pin "9") (pinfunction "GND_9") (pintype "power_in"))
      (node (ref "U34") (pin "2") (pinfunction "GND_2") (pintype "power_in"))
      (node (ref "U35") (pin "2") (pinfunction "GND_2") (pintype "power_in"))
      (node (ref "U8") (pin "2") (pinfunction "MODE_2") (pintype "input"))
      (node (ref "U8") (pin "6") (pinfunction "GND_6") (pintype "power_in"))
      (node (ref "U8") (pin "7") (pinfunction "Exposed_Thermal_Pad_7") (pintype "passive"))
      (node (ref "U9") (pin "4") (pinfunction "GND_4") (pintype "power_in"))
      (node (ref "U9") (pin "9") (pinfunction "GND_9") (pintype "power_in"))
    )
    (net (code "21") (name "Net-(C50-Input)") (class "Default")
      (node (ref "C50") (pin "1") (pinfunction "Input_1") (pintype "passive"))
      (node (ref "C51") (pin "1") (pinfunction "1_1") (pintype "passive"))
      (node (ref "L2") (pin "2") (pinfunction "2_2") (pintype "passive"))
      (node (ref "R37") (pin "2") (pinfunction "2_2") (pintype "passive"))
      (node (ref "U11") (pin "4") (pinfunction "FB1_4") (pintype "input"))
    )
    (net (code "22") (name "Net-(C50-Output)") (class "Default")
      (node (ref "C50") (pin "3") (pinfunction "Output_3") (pintype "passive"))
      (node (ref "C52") (pin "1") (pinfunction "1_1") (pintype "passive"))
      (node (ref "C55") (pin "2") (pinfunction "2_2") (pintype "passive"))
      (node (ref "U10") (pin "1") (pinfunction "EN_1") (pintype "input"))
      (node (ref "U10") (pin "2") (pinfunction "IN_2") (pintype "power_in"))
    )
    (net (code "23") (name "Net-(C85-Input)") (class "Default")
      (node (ref "C85") (pin "1") (pinfunction "Input_1") (pintype "passive"))
      (node (ref "C86") (pin "1") (pinfunction "1_1") (pintype "passive"))
      (node (ref "L4") (pin "2") (pinfunction "2_2") (pintype "passive"))
      (node (ref "R51") (pin "2") (pinfunction "2_2") (pintype "passive"))
      (node (ref "U16") (pin "4") (pinfunction "FB1_4") (pintype "input"))
    )
    (net (code "24") (name "Net-(C85-Output)") (class "Default")
      (node (ref "C85") (pin "3") (pinfunction "Output_3") (pintype "passive"))
      (node (ref "C87") (pin "1") (pinfunction "1_1") (pintype "passive"))
      (node (ref "C90") (pin "2") (pinfunction "2_2") (pintype "passive"))
      (node (ref "U15") (pin "1") (pinfunction "EN_1") (pintype "input"))
      (node (ref "U15") (pin "2") (pinfunction "IN_2") (pintype "power_in"))
    )
    (net (code "25") (name "Net-(D2-A)") (class "Default")
      (node (ref "D2") (pin "2") (pinfunction "A_2") (pintype "passive"))
      (node (ref "R34") (pin "1") (pinfunction "1_1") (pintype "passive"))
    )
    (net (code "26") (name "Net-(FB8-Input)") (class "Default")
      (node (ref "C34") (pin "1") (pinfunction "1_1") (pintype "passive"))
      (node (ref "C46") (pin "2") (pinfunction "2_2") (pintype "passive"))
      (node (ref "FB8") (pin "1") (pinfunction "Input_1") (pintype "passive"))
      (node (ref "L1") (pin "2") (pinfunction "2_2") (pintype "passive"))
      (node (ref "R32") (pin "2") (pinfunction "2_2") (pintype "passive"))
    )
    (net (code "27") (name "Net-(FB8-Output)") (class "Default")
      (node (ref "C37") (pin "2") (pinfunction "2_2") (pintype "passive"))
      (node (ref "C39") (pin "2") (pinfunction "2_2") (pintype "passive"))
      (node (ref "FB8") (pin "3") (pinfunction "Output_3") (pintype "passive"))
      (node (ref "U9") (pin "5") (pinfunction "EN_5") (pintype "input"))
      (node (ref "U9") (pin "7") (pinfunction "IN_7") (pintype "power_in"))
      (node (ref "U9") (pin "8") (pinfunction "IN_8") (pintype "power_in"))
    )
    (net (code "28") (name "Net-(FB9-Input)") (class "Default")
      (node (ref "C61") (pin "1") (pinfunction "1_1") (pintype "passive"))
      (node (ref "FB9") (pin "1") (pinfunction "Input_1") (pintype "passive"))
      (node (ref "L3") (pin "2") (pinfunction "2_2") (pintype "passive"))
      (node (ref "R105") (pin "2") (pinfunction "2_2") (pintype "passive"))
    )
    (net (code "29") (name "Net-(FB9-Output)") (class "Default")
      (node (ref "C325") (pin "1") (pinfunction "1_1") (pintype "passive"))
      (node (ref "C62") (pin "1") (pinfunction "1_1") (pintype "passive"))
      (node (ref "C63") (pin "2") (pinfunction "2_2") (pintype "passive"))
      (node (ref "C70") (pin "1") (pinfunction "1_1") (pintype "passive"))
      (node (ref "C77") (pin "1") (pinfunction "1_1") (pintype "passive"))
      (node (ref "FB9") (pin "3") (pinfunction "Output_3") (pintype "passive"))
      (node (ref "U12") (pin "1") (pinfunction "IN_1") (pintype "power_in"))
      (node (ref "U12") (pin "3") (pinfunction "EN_3") (pintype "input"))
      (node (ref "U13") (pin "1") (pinfunction "IN_1") (pintype "power_in"))
      (node (ref "U13") (pin "3") (pinfunction "EN_3") (pintype "input"))
      (node (ref "U34") (pin "1") (pinfunction "IN_1") (pintype "power_in"))
      (node (ref "U34") (pin "3") (pinfunction "EN_3") (pintype "input"))
    )
    (net (code "30") (name "Net-(FB14-Input)") (class "Default")
      (node (ref "C96") (pin "1") (pinfunction "1_1") (pintype "passive"))
      (node (ref "FB14") (pin "1") (pinfunction "Input_1") (pintype "passive"))
      (node (ref "L5") (pin "2") (pinfunction "2_2") (pintype "passive"))
      (node (ref "R123") (pin "2") (pinfunction "2_2") (pintype "passive"))
    )
    (net (code "31") (name "Net-(FB14-Output)") (class "Default")
      (node (ref "C105") (pin "1") (pinfunction "1_1") (pintype "passive"))
      (node (ref "C112") (pin "1") (pinfunction "1_1") (pintype "passive"))
      (node (ref "C332") (pin "1") (pinfunction "1_1") (pintype "passive"))
      (node (ref "C97") (pin "1") (pinfunction "1_1") (pintype "passive"))
      (node (ref "C98") (pin "2") (pinfunction "2_2") (pintype "passive"))
      (node (ref "FB14") (pin "3") (pinfunction "Output_3") (pintype "passive"))
      (node (ref "U17") (pin "1") (pinfunction "IN_1") (pintype "power_in"))
      (node (ref "U17") (pin "3") (pinfunction "EN_3") (pintype "input"))
      (node (ref "U18") (pin "1") (pinfunction "IN_1") (pintype "power_in"))
      (node (ref "U18") (pin "3") (pinfunction "EN_3") (pintype "input"))
      (node (ref "U35") (pin "1") (pinfunction "IN_1") (pintype "power_in"))
      (node (ref "U35") (pin "3") (pinfunction "EN_3") (pintype "input"))
    )
    (net (code "32") (name "Net-(FB24-Input)") (class "Default")
      (node (ref "C295") (pin "1") (pinfunction "1_1") (pintype "passive"))
      (node (ref "C299") (pin "2") (pinfunction "2_2") (pintype "passive"))
      (node (ref "FB24") (pin "1") (pinfunction "Input_1") (pintype "passive"))
      (node (ref "L70") (pin "2") (pinfunction "2_2") (pintype "passive"))
      (node (ref "R107") (pin "2") (pinfunction "2_2") (pintype "passive"))
    )
    (net (code "33") (name "Net-(FB24-Output)") (class "Default")
      (node (ref "C302") (pin "2") (pinfunction "2_2") (pintype "passive"))
      (node (ref "C304") (pin "2") (pinfunction "2_2") (pintype "passive"))
      (node (ref "FB24") (pin "3") (pinfunction "Output_3") (pintype "passive"))
      (node (ref "U33") (pin "5") (pinfunction "EN_5") (pintype "input"))
      (node (ref "U33") (pin "7") (pinfunction "IN_7") (pintype "power_in"))
      (node (ref "U33") (pin "8") (pinfunction "IN_8") (pintype "power_in"))
    )
    (net (code "34") (name "Net-(Q1-D)") (class "Default")
      (node (ref "J6") (pin "3") (pinfunction "3_3") (pintype "passive"))
      (node (ref "Q1") (pin "5-6-7-8") (pinfunction "D_5-6-7-8") (pintype "passive"))
      (node (ref "U14") (pin "5") (pinfunction "VIN_5") (pintype "input"))
    )
    (net (code "35") (name "Net-(Q1-G)") (class "Default")
      (node (ref "Q1") (pin "4") (pinfunction "G_4") (pintype "passive"))
      (node (ref "U14") (pin "4") (pinfunction "GATE_4") (pintype "output"))
    )
    (net (code "36") (name "Net-(U8-FB)") (class "Default")
      (node (ref "C34") (pin "2") (pinfunction "2_2") (pintype "passive"))
      (node (ref "R32") (pin "1") (pinfunction "1_1") (pintype "passive"))
      (node (ref "R36") (pin "2") (pinfunction "2_2") (pintype "passive"))
      (node (ref "U8") (pin "3") (pinfunction "FB_3") (pintype "input"))
    )
    (net (code "37") (name "Net-(U8-SW)") (class "Default")
      (node (ref "L1") (pin "1") (pinfunction "1_1") (pintype "passive"))
      (node (ref "U8") (pin "1") (pinfunction "SW_1") (pintype "passive"))
    )
    (net (code "38") (name "Net-(U9-FB)") (class "Default")
      (node (ref "R33") (pin "1") (pinfunction "1_1") (pintype "passive"))
      (node (ref "R35") (pin "2") (pinfunction "2_2") (pintype "passive"))
      (node (ref "U9") (pin "3") (pinfunction "FB_3") (pintype "input"))
    )
    (net (code "39") (name "Net-(U9-NR)") (class "Default")
      (node (ref "C44") (pin "1") (pinfunction "1_1") (pintype "passive"))
      (node (ref "U9") (pin "6") (pinfunction "NR_6") (pintype "passive"))
    )
    (net (code "40") (name "Net-(U10-NR)") (class "Default")
      (node (ref "C281") (pin "1") (pinfunction "1_1") (pintype "passive"))
      (node (ref "U10") (pin "5") (pinfunction "NR_5") (pintype "passive"))
    )
    (net (code "41") (name "Net-(U11-ADJ2)") (class "Default")
      (node (ref "R105") (pin "1") (pinfunction "1_1") (pintype "passive"))
      (node (ref "R41") (pin "2") (pinfunction "2_2") (pintype "passive"))
      (node (ref "U11") (pin "1") (pinfunction "ADJ2_1") (pintype "input"))
    )
    (net (code "42") (name "Net-(U11-SW1)") (class "Default")
      (node (ref "L2") (pin "1") (pinfunction "1_1") (pintype "passive"))
      (node (ref "U11") (pin "6") (pinfunction "SW1_6") (pintype "power_in"))
    )
    (net (code "43") (name "Net-(U11-SW2)") (class "Default")
      (node (ref "L3") (pin "1") (pinfunction "1_1") (pintype "passive"))
      (node (ref "U11") (pin "10") (pinfunction "SW2_10") (pintype "power_in"))
    )
    (net (code "44") (name "Net-(U12-FB)") (class "Default")
      (node (ref "R40") (pin "1") (pinfunction "1_1") (pintype "passive"))
      (node (ref "R42") (pin "2") (pinfunction "2_2") (pintype "passive"))
      (node (ref "U12") (pin "4") (pinfunction "FB_4") (pintype "input"))
    )
    (net (code "45") (name "Net-(U12-OUT)") (class "Default")
      (node (ref "C64") (pin "2") (pinfunction "2_2") (pintype "passive"))
      (node (ref "C65") (pin "1") (pinfunction "1_1") (pintype "passive"))
      (node (ref "C68") (pin "2") (pinfunction "2_2") (pintype "passive"))
      (node (ref "FB10") (pin "1") (pinfunction "1_1") (pintype "passive"))
      (node (ref "R40") (pin "2") (pinfunction "2_2") (pintype "passive"))
      (node (ref "U12") (pin "5") (pinfunction "OUT_5") (pintype "power_in"))
    )
    (net (code "46") (name "Net-(U13-FB)") (class "Default")
      (node (ref "R43") (pin "1") (pinfunction "1_1") (pintype "passive"))
      (node (ref "R44") (pin "2") (pinfunction "2_2") (pintype "passive"))
      (node (ref "U13") (pin "4") (pinfunction "FB_4") (pintype "input"))
    )
    (net (code "47") (name "Net-(U13-OUT)") (class "Default")
      (node (ref "C71") (pin "2") (pinfunction "2_2") (pintype "passive"))
      (node (ref "C72") (pin "1") (pinfunction "1_1") (pintype "passive"))
      (node (ref "C75") (pin "2") (pinfunction "2_2") (pintype "passive"))
      (node (ref "FB13") (pin "1") (pinfunction "1_1") (pintype "passive"))
      (node (ref "R43") (pin "2") (pinfunction "2_2") (pintype "passive"))
      (node (ref "U13") (pin "5") (pinfunction "OUT_5") (pintype "power_in"))
    )
    (net (code "48") (name "Net-(U15-NR)") (class "Default")
      (node (ref "C282") (pin "1") (pinfunction "1_1") (pintype "passive"))
      (node (ref "U15") (pin "5") (pinfunction "NR_5") (pintype "passive"))
    )
    (net (code "49") (name "Net-(U16-ADJ2)") (class "Default")
      (node (ref "R123") (pin "1") (pinfunction "1_1") (pintype "passive"))
      (node (ref "R55") (pin "2") (pinfunction "2_2") (pintype "passive"))
      (node (ref "U16") (pin "1") (pinfunction "ADJ2_1") (pintype "input"))
    )
    (net (code "50") (name "Net-(U16-SW1)") (class "Default")
      (node (ref "L4") (pin "1") (pinfunction "1_1") (pintype "passive"))
      (node (ref "U16") (pin "6") (pinfunction "SW1_6") (pintype "power_in"))
    )
    (net (code "51") (name "Net-(U16-SW2)") (class "Default")
      (node (ref "L5") (pin "1") (pinfunction "1_1") (pintype "passive"))
      (node (ref "U16") (pin "10") (pinfunction "SW2_10") (pintype "power_in"))
    )
    (net (code "52") (name "Net-(U17-FB)") (class "Default")
      (node (ref "R54") (pin "1") (pinfunction "1_1") (pintype "passive"))
      (node (ref "R56") (pin "2") (pinfunction "2_2") (pintype "passive"))
      (node (ref "U17") (pin "4") (pinfunction "FB_4") (pintype "input"))
    )
    (net (code "53") (name "Net-(U17-OUT)") (class "Default")
      (node (ref "C100") (pin "1") (pinfunction "1_1") (pintype "passive"))
      (node (ref "C103") (pin "2") (pinfunction "2_2") (pintype "passive"))
      (node (ref "C99") (pin "2") (pinfunction "2_2") (pintype "passive"))
      (node (ref "FB15") (pin "1") (pinfunction "1_1") (pintype "passive"))
      (node (ref "R54") (pin "2") (pinfunction "2_2") (pintype "passive"))
      (node (ref "U17") (pin "5") (pinfunction "OUT_5") (pintype "power_in"))
    )
    (net (code "54") (name "Net-(U18-FB)") (class "Default")
      (node (ref "R57") (pin "1") (pinfunction "1_1") (pintype "passive"))
      (node (ref "R58") (pin "2") (pinfunction "2_2") (pintype "passive"))
      (node (ref "U18") (pin "4") (pinfunction "FB_4") (pintype "input"))
    )
    (net (code "55") (name "Net-(U18-OUT)") (class "Default")
      (node (ref "C106") (pin "2") (pinfunction "2_2") (pintype "passive"))
      (node (ref "C107") (pin "1") (pinfunction "1_1") (pintype "passive"))
      (node (ref "C110") (pin "2") (pinfunction "2_2") (pintype "passive"))
      (node (ref "FB16") (pin "1") (pinfunction "1_1") (pintype "passive"))
      (node (ref "R57") (pin "2") (pinfunction "2_2") (pintype "passive"))
      (node (ref "U18") (pin "5") (pinfunction "OUT_5") (pintype "power_in"))
    )
    (net (code "56") (name "Net-(U19-SS)") (class "Default")
      (node (ref "C115") (pin "1") (pinfunction "1_1") (pintype "passive"))
      (node (ref "U19") (pin "8") (pinfunction "SS_8") (pintype "input"))
    )
    (net (code "57") (name "Net-(U20-SS)") (class "Default")
      (node (ref "C123") (pin "1") (pinfunction "1_1") (pintype "passive"))
      (node (ref "U20") (pin "8") (pinfunction "SS_8") (pintype "input"))
    )
    (net (code "58") (name "Net-(U21-SS)") (class "Default")
      (node (ref "C141") (pin "1") (pinfunction "1_1") (pintype "passive"))
      (node (ref "U21") (pin "8") (pinfunction "SS_8") (pintype "input"))
    )
    (net (code "59") (name "Net-(U32-FB)") (class "Default")
      (node (ref "C295") (pin "2") (pinfunction "2_2") (pintype "passive"))
      (node (ref "R107") (pin "1") (pinfunction "1_1") (pintype "passive"))
      (node (ref "R108") (pin "2") (pinfunction "2_2") (pintype "passive"))
      (node (ref "U32") (pin "3") (pinfunction "FB_3") (pintype "input"))
    )
    (net (code "60") (name "Net-(U32-SW)") (class "Default")
      (node (ref "L70") (pin "1") (pinfunction "1_1") (pintype "passive"))
      (node (ref "U32") (pin "1") (pinfunction "SW_1") (pintype "passive"))
    )
    (net (code "61") (name "Net-(U33-FB)") (class "Default")
      (node (ref "R109") (pin "1") (pinfunction "1_1") (pintype "passive"))
      (node (ref "R110") (pin "2") (pinfunction "2_2") (pintype "passive"))
      (node (ref "U33") (pin "3") (pinfunction "FB_3") (pintype "input"))
    )
    (net (code "62") (name "Net-(U33-NR)") (class "Default")
      (node (ref "C305") (pin "1") (pinfunction "1_1") (pintype "passive"))
      (node (ref "U33") (pin "6") (pinfunction "NR_6") (pintype "passive"))
    )
    (net (code "63") (name "Net-(U34-FB)") (class "Default")
      (node (ref "R106") (pin "1") (pinfunction "1_1") (pintype "passive"))
      (node (ref "R122") (pin "2") (pinfunction "2_2") (pintype "passive"))
      (node (ref "U34") (pin "4") (pinfunction "FB_4") (pintype "input"))
    )
    (net (code "64") (name "Net-(U34-OUT)") (class "Default")
      (node (ref "C290") (pin "2") (pinfunction "2_2") (pintype "passive"))
      (node (ref "C291") (pin "1") (pinfunction "1_1") (pintype "passive"))
      (node (ref "C294") (pin "2") (pinfunction "2_2") (pintype "passive"))
      (node (ref "FB26") (pin "1") (pinfunction "1_1") (pintype "passive"))
      (node (ref "R106") (pin "2") (pinfunction "2_2") (pintype "passive"))
      (node (ref "U34") (pin "5") (pinfunction "OUT_5") (pintype "power_in"))
    )
    (net (code "65") (name "Net-(U35-FB)") (class "Default")
      (node (ref "R124") (pin "1") (pinfunction "1_1") (pintype "passive"))
      (node (ref "R125") (pin "2") (pinfunction "2_2") (pintype "passive"))
      (node (ref "U35") (pin "4") (pinfunction "FB_4") (pintype "input"))
    )
    (net (code "66") (name "Net-(U35-OUT)") (class "Default")
      (node (ref "C326") (pin "2") (pinfunction "2_2") (pintype "passive"))
      (node (ref "C327") (pin "1") (pinfunction "1_1") (pintype "passive"))
      (node (ref "C330") (pin "2") (pinfunction "2_2") (pintype "passive"))
      (node (ref "FB27") (pin "1") (pinfunction "1_1") (pintype "passive"))
      (node (ref "R124") (pin "2") (pinfunction "2_2") (pintype "passive"))
      (node (ref "U35") (pin "5") (pinfunction "OUT_5") (pintype "power_in"))
    )
  )
)
